# 20200614.net
KiCad netlist of a schematic drawn in Altium Designer
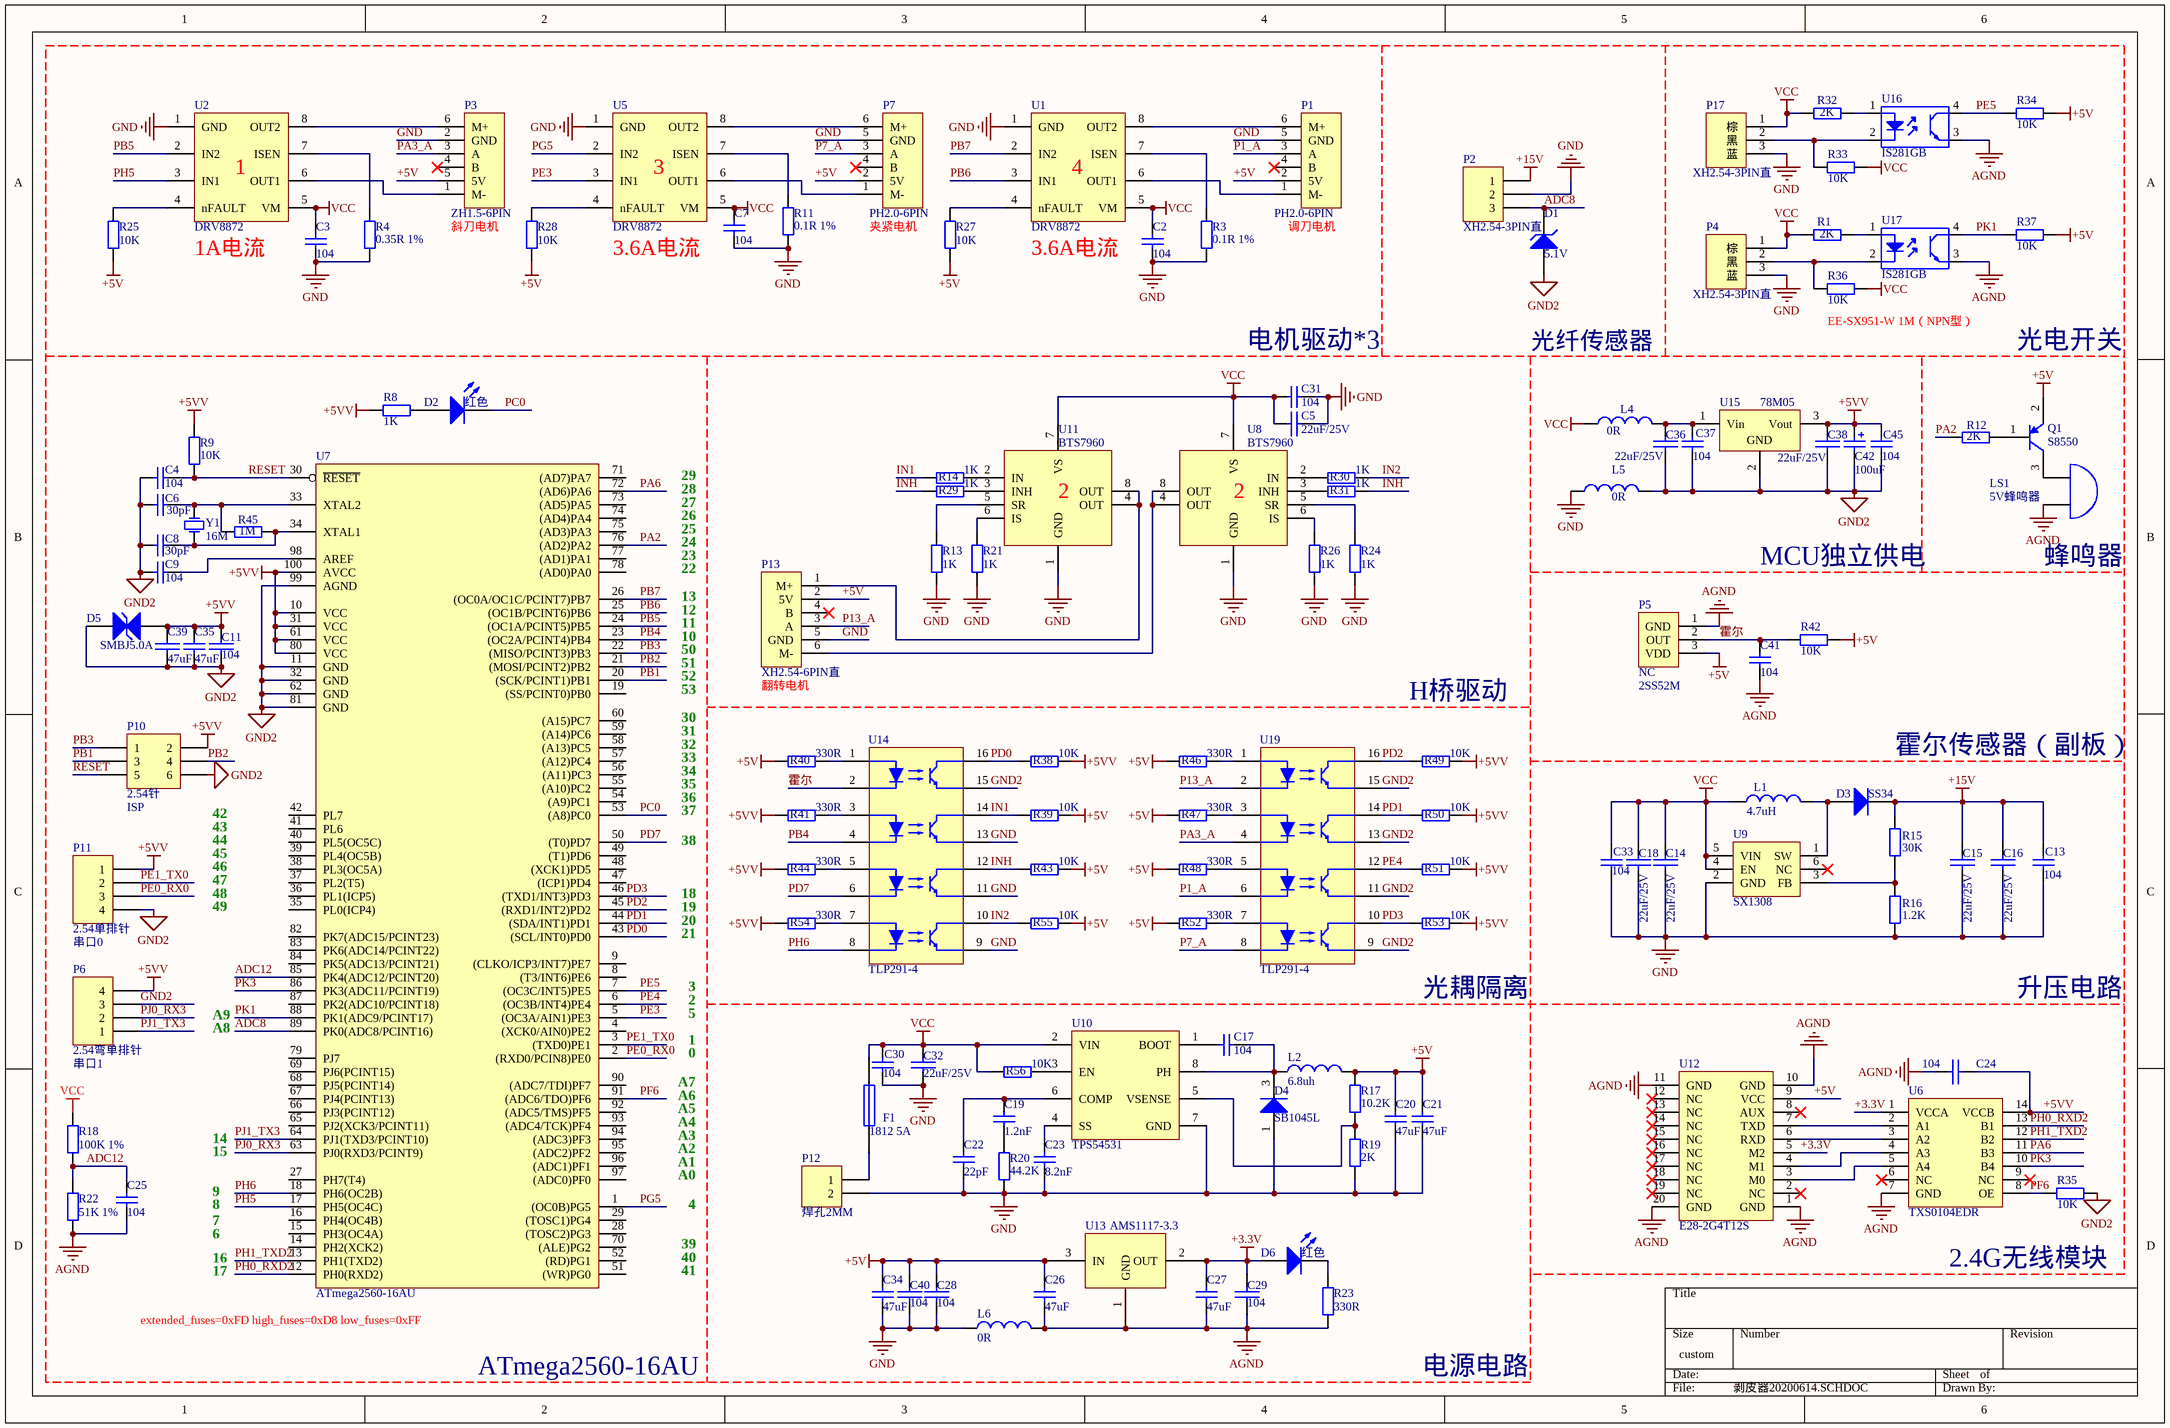
[diagram p0: 剥皮器20200614.SCHDOC]

(export (version "E")
  (design (tool "Eeschema 10.0.6"))
  (components
    (comp (ref "C2")
      (value "104")
      (footprint "0805-C")
      (description "Capacitor")
      (fields (field (name "PUBLISHER") "Altium Limited"))
      (libsource (lib "Miscellaneous Devices") (part "Cap"))
    )
    (comp (ref "C3")
      (value "104")
      (footprint "0805-C")
      (description "Capacitor")
      (fields (field (name "PUBLISHER") "Altium Limited"))
      (libsource (lib "Miscellaneous Devices") (part "Cap"))
    )
    (comp (ref "C4")
      (value "104")
      (footprint "0805-C")
      (description "Capacitor")
      (fields (field (name "PUBLISHER") "Altium Limited"))
      (libsource (lib "Miscellaneous Devices") (part "Cap"))
    )
    (comp (ref "C5")
      (value "22uF/25V")
      (footprint "1206-C")
      (description "Capacitor")
      (libsource (lib "*") (part "CAP"))
    )
    (comp (ref "C6")
      (value "30pF")
      (footprint "0805-C")
      (description "Capacitor")
      (fields (field (name "PUBLISHER") "Altium Limited"))
      (libsource (lib "Miscellaneous Devices") (part "Cap"))
    )
    (comp (ref "C7")
      (value "104")
      (footprint "0805-C")
      (description "Capacitor")
      (fields (field (name "PUBLISHER") "Altium Limited"))
      (libsource (lib "Miscellaneous Devices") (part "Cap"))
    )
    (comp (ref "C8")
      (value "30pF")
      (footprint "0805-C")
      (description "Capacitor")
      (fields (field (name "PUBLISHER") "Altium Limited"))
      (libsource (lib "Miscellaneous Devices") (part "Cap"))
    )
    (comp (ref "C9")
      (value "104")
      (footprint "0805-C")
      (description "Capacitor")
      (fields (field (name "PUBLISHER") "Altium Limited"))
      (libsource (lib "Miscellaneous Devices") (part "Cap"))
    )
    (comp (ref "C11")
      (value "104")
      (footprint "0805-C")
      (description "Capacitor")
      (libsource (lib "*") (part "CAP"))
    )
    (comp (ref "C13")
      (value "104")
      (footprint "0805-C")
      (description "Capacitor")
      (fields (field (name "PUBLISHER") "Altium Limited"))
      (libsource (lib "Miscellaneous Devices") (part "Cap"))
    )
    (comp (ref "C14")
      (value "22uF/25V")
      (footprint "1206-C")
      (description "Capacitor")
      (libsource (lib "*") (part "CAP"))
    )
    (comp (ref "C15")
      (value "22uF/25V")
      (footprint "1206-C")
      (description "Capacitor")
      (libsource (lib "*") (part "CAP"))
    )
    (comp (ref "C16")
      (value "22uF/25V")
      (footprint "1206-C")
      (description "Capacitor")
      (libsource (lib "*") (part "CAP"))
    )
    (comp (ref "C17")
      (value "104")
      (footprint "0805-C")
      (description "Capacitor")
      (fields (field (name "PUBLISHER") "Altium Limited"))
      (libsource (lib "Miscellaneous Devices") (part "Cap"))
    )
    (comp (ref "C18")
      (value "22uF/25V")
      (footprint "1206-C")
      (description "Capacitor")
      (libsource (lib "*") (part "CAP"))
    )
    (comp (ref "C19")
      (value "1.2nF")
      (footprint "0805-C")
      (description "Capacitor")
      (fields (field (name "PUBLISHER") "Altium Limited"))
      (libsource (lib "Miscellaneous Devices") (part "Cap"))
    )
    (comp (ref "C20")
      (value "47uF")
      (footprint "0805-C")
      (description "Capacitor")
      (fields (field (name "PUBLISHER") "Altium Limited"))
      (libsource (lib "Miscellaneous Devices") (part "Cap"))
    )
    (comp (ref "C21")
      (value "47uF")
      (footprint "0805-C")
      (description "Capacitor")
      (fields (field (name "PUBLISHER") "Altium Limited"))
      (libsource (lib "Miscellaneous Devices") (part "Cap"))
    )
    (comp (ref "C22")
      (value "22pF")
      (footprint "0805-C")
      (description "Capacitor")
      (fields (field (name "PUBLISHER") "Altium Limited"))
      (libsource (lib "Miscellaneous Devices") (part "Cap"))
    )
    (comp (ref "C23")
      (value "8.2nF")
      (footprint "0805-C")
      (description "Capacitor")
      (fields (field (name "PUBLISHER") "Altium Limited"))
      (libsource (lib "Miscellaneous Devices") (part "Cap"))
    )
    (comp (ref "C24")
      (value "104")
      (footprint "0805-C")
      (description "Capacitor")
      (libsource (lib "*") (part "CAP"))
    )
    (comp (ref "C25")
      (value "104")
      (footprint "0805-C")
      (description "Capacitor")
      (fields (field (name "PUBLISHER") "Altium Limited"))
      (libsource (lib "Miscellaneous Devices") (part "Cap"))
    )
    (comp (ref "C26")
      (value "47uF")
      (footprint "0805-C")
      (description "Capacitor")
      (fields (field (name "PUBLISHER") "Altium Limited"))
      (libsource (lib "Miscellaneous Devices") (part "Cap"))
    )
    (comp (ref "C27")
      (value "47uF")
      (footprint "0805-C")
      (description "Capacitor")
      (fields (field (name "PUBLISHER") "Altium Limited"))
      (libsource (lib "Miscellaneous Devices") (part "Cap"))
    )
    (comp (ref "C28")
      (value "104")
      (footprint "0805-C")
      (description "Capacitor")
      (libsource (lib "*") (part "CAP"))
    )
    (comp (ref "C29")
      (value "104")
      (footprint "0805-C")
      (description "Capacitor")
      (libsource (lib "*") (part "CAP"))
    )
    (comp (ref "C30")
      (value "104")
      (footprint "0805-C")
      (description "Capacitor")
      (fields (field (name "PUBLISHER") "Altium Limited"))
      (libsource (lib "Miscellaneous Devices") (part "Cap"))
    )
    (comp (ref "C31")
      (value "104")
      (footprint "0805-C")
      (description "Capacitor")
      (fields (field (name "PUBLISHER") "Altium Limited"))
      (libsource (lib "Miscellaneous Devices") (part "Cap"))
    )
    (comp (ref "C32")
      (value "22uF/25V")
      (footprint "1206-C")
      (description "Capacitor")
      (libsource (lib "*") (part "CAP"))
    )
    (comp (ref "C33")
      (value "104")
      (footprint "0805-C")
      (description "Capacitor")
      (fields (field (name "PUBLISHER") "Altium Limited"))
      (libsource (lib "Miscellaneous Devices") (part "Cap"))
    )
    (comp (ref "C34")
      (value "47uF")
      (footprint "0805-C")
      (description "Capacitor")
      (fields (field (name "PUBLISHER") "Altium Limited"))
      (libsource (lib "Miscellaneous Devices") (part "Cap"))
    )
    (comp (ref "C35")
      (value "47uF")
      (footprint "0805-C")
      (description "Capacitor")
      (fields (field (name "PUBLISHER") "Altium Limited"))
      (libsource (lib "Miscellaneous Devices") (part "Cap"))
    )
    (comp (ref "C36")
      (value "22uF/25V")
      (footprint "1206-C")
      (description "Capacitor")
      (libsource (lib "*") (part "CAP"))
    )
    (comp (ref "C37")
      (value "104")
      (footprint "0805-C")
      (description "Capacitor")
      (fields (field (name "PUBLISHER") "Altium Limited"))
      (libsource (lib "Miscellaneous Devices") (part "Cap"))
    )
    (comp (ref "C38")
      (value "22uF/25V")
      (footprint "1206-C")
      (description "Capacitor")
      (libsource (lib "*") (part "CAP"))
    )
    (comp (ref "C39")
      (value "47uF")
      (footprint "0805-C")
      (description "Capacitor")
      (libsource (lib "*") (part "CAP"))
    )
    (comp (ref "C40")
      (value "104")
      (footprint "0805-C")
      (description "Capacitor")
      (libsource (lib "*") (part "CAP"))
    )
    (comp (ref "C41")
      (value "104")
      (footprint "0805-C")
      (description "Capacitor")
      (fields (field (name "PUBLISHER") "Altium Limited"))
      (libsource (lib "Miscellaneous Devices") (part "Cap"))
    )
    (comp (ref "C42")
      (value "100uF")
      (footprint "LC-CASE-C_6032")
      (description "Polarized Capacitor (Axial)")
      (fields (field (name "PUBLISHER") "Altium Limited"))
      (libsource (lib "Miscellaneous Devices") (part "Cap Pol2"))
    )
    (comp (ref "C45")
      (value "104")
      (footprint "0805-C")
      (description "Capacitor")
      (fields (field (name "PUBLISHER") "Altium Limited"))
      (libsource (lib "Miscellaneous Devices") (part "Cap"))
    )
    (comp (ref "D1")
      (value "5.1V")
      (footprint "LC-LL-34")
      (description "Zener Diode")
      (fields (field (name "PUBLISHER") "Altium Limited"))
      (libsource (lib "Miscellaneous Devices") (part "D Zener"))
    )
    (comp (ref "D2")
      (value "红色")
      (footprint "0805-LED")
      (description "Typical INFRARED GaAs LED")
      (fields (field (name "PUBLISHER") "Altium Limited"))
      (libsource (lib "Miscellaneous Devices") (part "LED0"))
    )
    (comp (ref "D3")
      (value "SS34")
      (footprint "SMA - JW")
      (description "1 Amp General Purpose Rectifier")
      (fields (field (name "PUBLISHER") "Altium Limited"))
      (libsource (lib "Miscellaneous Devices") (part "Diode 1N4007"))
    )
    (comp (ref "D4")
      (value "SB1045L")
      (footprint "TO-277")
      (description "1 Amp General Purpose Rectifier")
      (fields (field (name "PUBLISHER") "Altium Limited"))
      (libsource (lib "Miscellaneous Devices") (part "Diode 1N4001"))
    )
    (comp (ref "D5")
      (value "SMBJ5.0A")
      (footprint "LC-SMB(DO-214AA)_S2")
      (description "TVS")
      (libsource (lib "JW专用元件库") (part "TVS"))
    )
    (comp (ref "D6")
      (value "红色")
      (footprint "0805-LED")
      (description "Typical INFRARED GaAs LED")
      (fields (field (name "PUBLISHER") "Altium Limited"))
      (libsource (lib "Miscellaneous Devices") (part "LED0"))
    )
    (comp (ref "F1")
      (value "1812 5A")
      (footprint "LC-1812_R")
      (description "Fuse")
      (fields (field (name "PUBLISHER") "Altium Limited"))
      (libsource (lib "Miscellaneous Devices") (part "Fuse 1"))
    )
    (comp (ref "L1")
      (value "4.7uH")
      (footprint "7*7*4电感")
      (description "Inductor")
      (fields (field (name "PUBLISHER") "Altium Limited"))
      (libsource (lib "Miscellaneous Devices") (part "Inductor"))
    )
    (comp (ref "L2")
      (value "6.8uh")
      (footprint "7*7*4电感")
      (description "Inductor")
      (fields (field (name "PUBLISHER") "Altium Limited"))
      (libsource (lib "Miscellaneous Devices") (part "Inductor"))
    )
    (comp (ref "L4")
      (value "0R")
      (footprint "0805-R")
      (description "Inductor")
      (fields (field (name "PUBLISHER") "Altium Limited"))
      (libsource (lib "Miscellaneous Devices") (part "Inductor"))
    )
    (comp (ref "L5")
      (value "0R")
      (footprint "0805-R")
      (description "Inductor")
      (fields (field (name "PUBLISHER") "Altium Limited"))
      (libsource (lib "Miscellaneous Devices") (part "Inductor"))
    )
    (comp (ref "L6")
      (value "0R")
      (footprint "0805-R")
      (description "Inductor")
      (fields (field (name "PUBLISHER") "Altium Limited"))
      (libsource (lib "Miscellaneous Devices") (part "Inductor"))
    )
    (comp (ref "LS1")
      (value "5V蜂鸣器")
      (footprint "蜂鸣器0905")
      (description "Electrical Bell")
      (fields (field (name "PUBLISHER") "Altium Limited"))
      (libsource (lib "Miscellaneous Devices") (part "Bell"))
    )
    (comp (ref "P1")
      (value "PH2.0-6PIN")
      (footprint "PH2.0-6PIN")
      (description "Header, 6-Pin")
      (fields (field (name "PUBLISHER") "Altium Limited"))
      (libsource (lib "Miscellaneous Connectors") (part "Header 6"))
    )
    (comp (ref "P2")
      (value "XH2.54-3PIN直")
      (footprint "XH2.54-3PIN直")
      (description "Header, 3-Pin")
      (fields (field (name "PUBLISHER") "Altium Limited"))
      (libsource (lib "") (part "Header 3_2"))
    )
    (comp (ref "P3")
      (value "ZH1.5-6PIN")
      (footprint "ZH1.5-6PIN")
      (description "Header, 6-Pin")
      (fields (field (name "PUBLISHER") "Altium Limited"))
      (libsource (lib "") (part "Header 6_2"))
    )
    (comp (ref "P4")
      (value "XH2.54-3PIN直")
      (footprint "XH2.54-3PIN直")
      (description "Header, 3-Pin")
      (fields (field (name "PUBLISHER") "Altium Limited"))
      (libsource (lib "") (part "Header 3_1"))
    )
    (comp (ref "P5")
      (value "NC")
      (footprint "TO-92—_三极管")
      (description "Header, 3-Pin")
      (fields (field (name "PUBLISHER") "2SS52M"))
      (libsource (lib "Miscellaneous Connectors") (part "Header 3"))
    )
    (comp (ref "P6")
      (value "2.54弯单排针")
      (footprint "HDR1X4H")
      (description "Header, 4-Pin")
      (fields (field (name "ALTIUM_UNNAMED_1") "串口1") (field (name "PUBLISHER") "Altium Limited"))
      (libsource (lib "Miscellaneous Connectors") (part "Header 4"))
    )
    (comp (ref "P7")
      (value "PH2.0-6PIN")
      (footprint "PH2.0-6PIN")
      (description "Header, 6-Pin")
      (fields (field (name "PUBLISHER") "Altium Limited"))
      (libsource (lib "Miscellaneous Connectors") (part "Header 6"))
    )
    (comp (ref "P10")
      (value "2.54针")
      (footprint "HDR2X3")
      (description "Header, 3-Pin, Dual row")
      (fields (field (name "ALTIUM_UNNAMED_1") "ISP") (field (name "PUBLISHER") "Altium Limited"))
      (libsource (lib "Miscellaneous Connectors") (part "Header 3X2"))
    )
    (comp (ref "P11")
      (value "2.54单排针")
      (footprint "HDR1X4")
      (description "Header, 4-Pin")
      (fields (field (name "ALTIUM_UNNAMED_1") "串口0") (field (name "PUBLISHER") "Altium Limited"))
      (libsource (lib "") (part "Header 4_1"))
    )
    (comp (ref "P12")
      (value "焊孔2MM")
      (footprint "HDR1X2")
      (description "Header, 2-Pin")
      (fields (field (name "PUBLISHER") "Altium Limited"))
      (libsource (lib "Miscellaneous Connectors") (part "Header 2"))
    )
    (comp (ref "P13")
      (value "XH2.54-6PIN直")
      (footprint "XH2.54-6PIN直")
      (description "Header, 6-Pin")
      (fields (field (name "PUBLISHER") "Altium Limited"))
      (libsource (lib "") (part "Header 6_1"))
    )
    (comp (ref "P17")
      (value "XH2.54-3PIN直")
      (footprint "XH2.54-3PIN直")
      (description "Header, 3-Pin")
      (fields (field (name "PUBLISHER") "Altium Limited"))
      (libsource (lib "") (part "Header 3_1"))
    )
    (comp (ref "Q1")
      (value "S8550")
      (footprint "SOT--23")
      (description "PNP General Purpose Amplifier")
      (fields (field (name "PUBLISHER") "Altium Limited"))
      (libsource (lib "Miscellaneous Devices") (part "2N3906"))
    )
    (comp (ref "R1")
      (value "2K")
      (footprint "0805-R")
      (description "Resistor")
      (fields (field (name "PUBLISHER") "Altium Limited"))
      (libsource (lib "") (part "Res2_2"))
    )
    (comp (ref "R3")
      (value "0.1R 1%")
      (footprint "2512-R")
      (description "Resistor")
      (fields (field (name "PUBLISHER") "Altium Limited"))
      (libsource (lib "Miscellaneous Devices") (part "Res2"))
    )
    (comp (ref "R4")
      (value "0.35R 1%")
      (footprint "2512-R")
      (description "Resistor")
      (fields (field (name "PUBLISHER") "Altium Limited"))
      (libsource (lib "Miscellaneous Devices") (part "Res2"))
    )
    (comp (ref "R8")
      (value "1K")
      (footprint "0805-R")
      (description "Resistor")
      (fields (field (name "PUBLISHER") "Altium Limited"))
      (libsource (lib "") (part "Res2_1"))
    )
    (comp (ref "R9")
      (value "10K")
      (footprint "0805-R")
      (description "Resistor")
      (fields (field (name "PUBLISHER") "Altium Limited"))
      (libsource (lib "Miscellaneous Devices") (part "Res2"))
    )
    (comp (ref "R11")
      (value "0.1R 1%")
      (footprint "2512-R")
      (description "Resistor")
      (fields (field (name "PUBLISHER") "Altium Limited"))
      (libsource (lib "Miscellaneous Devices") (part "Res2"))
    )
    (comp (ref "R12")
      (value "2K")
      (footprint "0805-R")
      (description "Resistor")
      (fields (field (name "PUBLISHER") "Altium Limited"))
      (libsource (lib "") (part "Res2_1"))
    )
    (comp (ref "R13")
      (value "1K")
      (footprint "0805-R")
      (description "Resistor")
      (fields (field (name "PUBLISHER") "Altium Limited"))
      (libsource (lib "Miscellaneous Devices") (part "Res2"))
    )
    (comp (ref "R14")
      (value "1K")
      (footprint "0805-R")
      (description "Resistor")
      (fields (field (name "PUBLISHER") "Altium Limited"))
      (libsource (lib "") (part "Res2_1"))
    )
    (comp (ref "R15")
      (value "30K")
      (footprint "0805-R")
      (description "Resistor")
      (fields (field (name "PUBLISHER") "Altium Limited"))
      (libsource (lib "") (part "Res2_3"))
    )
    (comp (ref "R16")
      (value "1.2K")
      (footprint "0805-R")
      (description "Resistor")
      (fields (field (name "PUBLISHER") "Altium Limited"))
      (libsource (lib "") (part "Res2_3"))
    )
    (comp (ref "R17")
      (value "10.2K")
      (footprint "0805-R")
      (description "Resistor")
      (fields (field (name "PUBLISHER") "Altium Limited"))
      (libsource (lib "Miscellaneous Devices") (part "Res2"))
    )
    (comp (ref "R18")
      (value "100K 1%")
      (footprint "0805-R")
      (description "Resistor")
      (fields (field (name "PUBLISHER") "Altium Limited"))
      (libsource (lib "Miscellaneous Devices") (part "Res2"))
    )
    (comp (ref "R19")
      (value "2K")
      (footprint "0805-R")
      (description "Resistor")
      (fields (field (name "PUBLISHER") "Altium Limited"))
      (libsource (lib "Miscellaneous Devices") (part "Res2"))
    )
    (comp (ref "R20")
      (value "44.2K")
      (footprint "0805-R")
      (description "Resistor")
      (fields (field (name "PUBLISHER") "Altium Limited"))
      (libsource (lib "Miscellaneous Devices") (part "Res2"))
    )
    (comp (ref "R21")
      (value "1K")
      (footprint "0805-R")
      (description "Resistor")
      (fields (field (name "PUBLISHER") "Altium Limited"))
      (libsource (lib "Miscellaneous Devices") (part "Res2"))
    )
    (comp (ref "R22")
      (value "51K 1%")
      (footprint "0805-R")
      (description "Resistor")
      (fields (field (name "PUBLISHER") "Altium Limited"))
      (libsource (lib "Miscellaneous Devices") (part "Res2"))
    )
    (comp (ref "R23")
      (value "330R")
      (footprint "0805-R")
      (description "Resistor")
      (fields (field (name "PUBLISHER") "Altium Limited"))
      (libsource (lib "") (part "Res2_3"))
    )
    (comp (ref "R24")
      (value "1K")
      (footprint "0805-R")
      (description "Resistor")
      (fields (field (name "PUBLISHER") "Altium Limited"))
      (libsource (lib "") (part "Res2_2"))
    )
    (comp (ref "R25")
      (value "10K")
      (footprint "0805-R")
      (description "Resistor")
      (fields (field (name "PUBLISHER") "Altium Limited"))
      (libsource (lib "Miscellaneous Devices") (part "Res2"))
    )
    (comp (ref "R26")
      (value "1K")
      (footprint "0805-R")
      (description "Resistor")
      (fields (field (name "PUBLISHER") "Altium Limited"))
      (libsource (lib "") (part "Res2_2"))
    )
    (comp (ref "R27")
      (value "10K")
      (footprint "0805-R")
      (description "Resistor")
      (fields (field (name "PUBLISHER") "Altium Limited"))
      (libsource (lib "Miscellaneous Devices") (part "Res2"))
    )
    (comp (ref "R28")
      (value "10K")
      (footprint "0805-R")
      (description "Resistor")
      (fields (field (name "PUBLISHER") "Altium Limited"))
      (libsource (lib "Miscellaneous Devices") (part "Res2"))
    )
    (comp (ref "R29")
      (value "1K")
      (footprint "0805-R")
      (description "Resistor")
      (fields (field (name "PUBLISHER") "Altium Limited"))
      (libsource (lib "") (part "Res2_1"))
    )
    (comp (ref "R30")
      (value "1K")
      (footprint "0805-R")
      (description "Resistor")
      (fields (field (name "PUBLISHER") "Altium Limited"))
      (libsource (lib "") (part "Res2_1"))
    )
    (comp (ref "R31")
      (value "1K")
      (footprint "0805-R")
      (description "Resistor")
      (fields (field (name "PUBLISHER") "Altium Limited"))
      (libsource (lib "") (part "Res2_1"))
    )
    (comp (ref "R32")
      (value "2K")
      (footprint "0805-R")
      (description "Resistor")
      (fields (field (name "PUBLISHER") "Altium Limited"))
      (libsource (lib "") (part "Res2_2"))
    )
    (comp (ref "R33")
      (value "10K")
      (footprint "0805-R")
      (description "Resistor")
      (fields (field (name "PUBLISHER") "Altium Limited"))
      (libsource (lib "") (part "Res2_1"))
    )
    (comp (ref "R34")
      (value "10K")
      (footprint "0805-R")
      (description "Resistor")
      (fields (field (name "PUBLISHER") "Altium Limited"))
      (libsource (lib "") (part "Res2_2"))
    )
    (comp (ref "R35")
      (value "10K")
      (footprint "0805-R")
      (description "Resistor")
      (fields (field (name "PUBLISHER") "Altium Limited"))
      (libsource (lib "") (part "Res2_1"))
    )
    (comp (ref "R36")
      (value "10K")
      (footprint "0805-R")
      (description "Resistor")
      (fields (field (name "PUBLISHER") "Altium Limited"))
      (libsource (lib "") (part "Res2_1"))
    )
    (comp (ref "R37")
      (value "10K")
      (footprint "0805-R")
      (description "Resistor")
      (fields (field (name "PUBLISHER") "Altium Limited"))
      (libsource (lib "") (part "Res2_2"))
    )
    (comp (ref "R38")
      (value "10K")
      (footprint "0805-R")
      (description "Resistor")
      (fields (field (name "PUBLISHER") "Altium Limited"))
      (libsource (lib "") (part "Res2_1"))
    )
    (comp (ref "R39")
      (value "10K")
      (footprint "0805-R")
      (description "Resistor")
      (fields (field (name "PUBLISHER") "Altium Limited"))
      (libsource (lib "") (part "Res2_1"))
    )
    (comp (ref "R40")
      (value "330R")
      (footprint "0805-R")
      (description "Resistor")
      (fields (field (name "PUBLISHER") "Altium Limited"))
      (libsource (lib "") (part "Res2_1"))
    )
    (comp (ref "R41")
      (value "330R")
      (footprint "0805-R")
      (description "Resistor")
      (fields (field (name "PUBLISHER") "Altium Limited"))
      (libsource (lib "") (part "Res2_1"))
    )
    (comp (ref "R42")
      (value "10K")
      (footprint "0805-R")
      (description "Resistor")
      (fields (field (name "PUBLISHER") "Altium Limited"))
      (libsource (lib "") (part "Res2_1"))
    )
    (comp (ref "R43")
      (value "10K")
      (footprint "0805-R")
      (description "Resistor")
      (fields (field (name "PUBLISHER") "Altium Limited"))
      (libsource (lib "") (part "Res2_1"))
    )
    (comp (ref "R44")
      (value "330R")
      (footprint "0805-R")
      (description "Resistor")
      (fields (field (name "PUBLISHER") "Altium Limited"))
      (libsource (lib "") (part "Res2_1"))
    )
    (comp (ref "R45")
      (value "1M")
      (footprint "0805-R")
      (description "Resistor")
      (fields (field (name "PUBLISHER") "Altium Limited"))
      (libsource (lib "") (part "Res2_2"))
    )
    (comp (ref "R46")
      (value "330R")
      (footprint "0805-R")
      (description "Resistor")
      (fields (field (name "PUBLISHER") "Altium Limited"))
      (libsource (lib "") (part "Res2_1"))
    )
    (comp (ref "R47")
      (value "330R")
      (footprint "0805-R")
      (description "Resistor")
      (fields (field (name "PUBLISHER") "Altium Limited"))
      (libsource (lib "") (part "Res2_1"))
    )
    (comp (ref "R48")
      (value "330R")
      (footprint "0805-R")
      (description "Resistor")
      (fields (field (name "PUBLISHER") "Altium Limited"))
      (libsource (lib "") (part "Res2_1"))
    )
    (comp (ref "R49")
      (value "10K")
      (footprint "0805-R")
      (description "Resistor")
      (fields (field (name "PUBLISHER") "Altium Limited"))
      (libsource (lib "") (part "Res2_1"))
    )
    (comp (ref "R50")
      (value "10K")
      (footprint "0805-R")
      (description "Resistor")
      (fields (field (name "PUBLISHER") "Altium Limited"))
      (libsource (lib "") (part "Res2_1"))
    )
    (comp (ref "R51")
      (value "10K")
      (footprint "0805-R")
      (description "Resistor")
      (fields (field (name "PUBLISHER") "Altium Limited"))
      (libsource (lib "") (part "Res2_1"))
    )
    (comp (ref "R52")
      (value "330R")
      (footprint "0805-R")
      (description "Resistor")
      (fields (field (name "PUBLISHER") "Altium Limited"))
      (libsource (lib "") (part "Res2_1"))
    )
    (comp (ref "R53")
      (value "10K")
      (footprint "0805-R")
      (description "Resistor")
      (fields (field (name "PUBLISHER") "Altium Limited"))
      (libsource (lib "") (part "Res2_1"))
    )
    (comp (ref "R54")
      (value "330R")
      (footprint "0805-R")
      (description "Resistor")
      (fields (field (name "PUBLISHER") "Altium Limited"))
      (libsource (lib "") (part "Res2_1"))
    )
    (comp (ref "R55")
      (value "10K")
      (footprint "0805-R")
      (description "Resistor")
      (fields (field (name "PUBLISHER") "Altium Limited"))
      (libsource (lib "") (part "Res2_1"))
    )
    (comp (ref "R56")
      (value "10K")
      (footprint "0805-R")
      (description "Resistor")
      (fields (field (name "PUBLISHER") "Altium Limited"))
      (libsource (lib "") (part "Res2_1"))
    )
    (comp (ref "U1")
      (value "DRV8872")
      (footprint "SOP-8带散热")
      (description "6N137")
      (libsource (lib "JW专用库") (part "6N137"))
    )
    (comp (ref "U2")
      (value "DRV8872")
      (footprint "SOP-8带散热")
      (description "6N137")
      (libsource (lib "JW专用库") (part "6N137"))
    )
    (comp (ref "U5")
      (value "DRV8872")
      (footprint "SOP-8带散热")
      (description "6N137")
      (libsource (lib "JW专用库") (part "6N137"))
    )
    (comp (ref "U6")
      (value "TXS0104EDR")
      (footprint "LC-SOIC-14_150mil")
      (libsource (lib "*") (part "TXS0104EDR"))
    )
    (comp (ref "U7")
      (value "ATmega2560-16AU")
      (footprint "LC-LQFP-100_14x14x05P")
      (libsource (lib "*") (part "Arduino MEGA 2560"))
    )
    (comp (ref "U8") (value "BTS7960") (footprint "LC-TO-263-7") (libsource (lib "") (part "BTS7960_1")))
    (comp (ref "U9") (value "SX1308") (footprint "SOT-23-6") (libsource (lib "JW专用库") (part "SX1308")))
    (comp (ref "U10") (value "TPS54531") (footprint "SOP-8带散热") (libsource (lib "*") (part "TPS54531")))
    (comp (ref "U11") (value "BTS7960") (footprint "LC-TO-263-7") (libsource (lib "*") (part "BTS7960")))
    (comp (ref "U12")
      (value "E28-2G4T12S")
      (footprint "E28-2G4T12S")
      (libsource (lib "JW专用元件库") (part "E43-433T13S"))
    )
    (comp (ref "U13") (value "AMS1117-3.3") (footprint "SOT--223") (libsource (lib "*") (part "AS1117")))
    (comp (ref "U14")
      (value "TLP291-4")
      (footprint "TLP291-4")
      (description "Photocouplers GaAs Infrared LED & Photo Transistor")
      (libsource (lib "YS_STM32F407_MC") (part "TLP291-4"))
    )
    (comp (ref "U15")
      (value "78M05")
      (footprint "TO-252")
      (description "Voltage Regulator")
      (fields (field (name "PUBLISHER") "Altium Limited"))
      (libsource (lib "Miscellaneous Devices") (part "Volt Reg"))
    )
    (comp (ref "U16") (value "IS281GB") (footprint "LC-SOP-4_P1.27") (libsource (lib "*") (part "TLP521-1")))
    (comp (ref "U17") (value "IS281GB") (footprint "LC-SOP-4_P1.27") (libsource (lib "*") (part "TLP521-1")))
    (comp (ref "U19")
      (value "TLP291-4")
      (footprint "TLP291-4")
      (description "Photocouplers GaAs Infrared LED & Photo Transistor")
      (libsource (lib "YS_STM32F407_MC") (part "TLP291-4"))
    )
    (comp (ref "Y1")
      (value "16M")
      (footprint "LC-SMD-5032_2P")
      (description "Crystal Oscillator")
      (fields (field (name "PUBLISHER") "Altium Limited"))
      (libsource (lib "Miscellaneous Devices") (part "XTAL"))
    )
  )
  (nets
    (net (code "1") (name "+3.3V") (class "Default")
      (node (ref "C27") (pin "2") (pinfunction "2_2") (pintype "passive"))
      (node (ref "C29") (pin "1") (pinfunction "1_1") (pintype "passive"))
      (node (ref "D6") (pin "1") (pinfunction "A_1") (pintype "passive"))
      (node (ref "U12") (pin "5") (pinfunction "M2_5") (pintype "passive"))
      (node (ref "U13") (pin "2") (pinfunction "OUT_2") (pintype "passive"))
      (node (ref "U6") (pin "1") (pinfunction "VCCA_1") (pintype "passive"))
    )
    (net (code "2") (name "+5V") (class "Default")
      (node (ref "C20") (pin "2") (pinfunction "2_2") (pintype "passive"))
      (node (ref "C21") (pin "2") (pinfunction "2_2") (pintype "passive"))
      (node (ref "C26") (pin "2") (pinfunction "2_2") (pintype "passive"))
      (node (ref "C28") (pin "1") (pinfunction "1_1") (pintype "passive"))
      (node (ref "C34") (pin "2") (pinfunction "2_2") (pintype "passive"))
      (node (ref "C40") (pin "1") (pinfunction "1_1") (pintype "passive"))
      (node (ref "L2") (pin "2") (pinfunction "2_2") (pintype "passive"))
      (node (ref "P1") (pin "2") (pinfunction "5V_2") (pintype "passive"))
      (node (ref "P13") (pin "2") (pinfunction "5V_2") (pintype "passive"))
      (node (ref "P3") (pin "5") (pinfunction "5V_5") (pintype "passive"))
      (node (ref "P5") (pin "3") (pinfunction "VDD_3") (pintype "passive"))
      (node (ref "P7") (pin "2") (pinfunction "5V_2") (pintype "passive"))
      (node (ref "Q1") (pin "2") (pinfunction "E_2") (pintype "passive"))
      (node (ref "R17") (pin "2") (pinfunction "2_2") (pintype "passive"))
      (node (ref "R25") (pin "1") (pinfunction "1_1") (pintype "passive"))
      (node (ref "R27") (pin "1") (pinfunction "1_1") (pintype "passive"))
      (node (ref "R28") (pin "1") (pinfunction "1_1") (pintype "passive"))
      (node (ref "R34") (pin "2") (pinfunction "2_2") (pintype "passive"))
      (node (ref "R37") (pin "2") (pinfunction "2_2") (pintype "passive"))
      (node (ref "R39") (pin "1") (pinfunction "1_1") (pintype "passive"))
      (node (ref "R40") (pin "2") (pinfunction "2_2") (pintype "passive"))
      (node (ref "R42") (pin "1") (pinfunction "1_1") (pintype "passive"))
      (node (ref "R43") (pin "1") (pinfunction "1_1") (pintype "passive"))
      (node (ref "R46") (pin "2") (pinfunction "2_2") (pintype "passive"))
      (node (ref "R47") (pin "2") (pinfunction "2_2") (pintype "passive"))
      (node (ref "R48") (pin "2") (pinfunction "2_2") (pintype "passive"))
      (node (ref "R52") (pin "2") (pinfunction "2_2") (pintype "passive"))
      (node (ref "R55") (pin "1") (pinfunction "1_1") (pintype "passive"))
      (node (ref "U12") (pin "9") (pinfunction "VCC_9") (pintype "passive"))
      (node (ref "U13") (pin "3") (pinfunction "IN_3") (pintype "passive"))
    )
    (net (code "3") (name "+5VV") (class "Default")
      (node (ref "C11") (pin "1") (pinfunction "1_1") (pintype "passive"))
      (node (ref "C24") (pin "2") (pinfunction "2_2") (pintype "passive"))
      (node (ref "C35") (pin "2") (pinfunction "2_2") (pintype "passive"))
      (node (ref "C38") (pin "1") (pinfunction "1_1") (pintype "passive"))
      (node (ref "C39") (pin "2") (pinfunction "2_2") (pintype "passive"))
      (node (ref "C42") (pin "1") (pinfunction "1_1") (pintype "passive"))
      (node (ref "C45") (pin "2") (pinfunction "2_2") (pintype "passive"))
      (node (ref "D5") (pin "1") (pinfunction "A_1") (pintype "passive"))
      (node (ref "P10") (pin "2") (pinfunction "2_2") (pintype "passive"))
      (node (ref "P11") (pin "1") (pinfunction "1_1") (pintype "passive"))
      (node (ref "P6") (pin "4") (pinfunction "4_4") (pintype "passive"))
      (node (ref "R38") (pin "1") (pinfunction "1_1") (pintype "passive"))
      (node (ref "R41") (pin "2") (pinfunction "2_2") (pintype "passive"))
      (node (ref "R44") (pin "2") (pinfunction "2_2") (pintype "passive"))
      (node (ref "R49") (pin "1") (pinfunction "1_1") (pintype "passive"))
      (node (ref "R50") (pin "1") (pinfunction "1_1") (pintype "passive"))
      (node (ref "R51") (pin "1") (pinfunction "1_1") (pintype "passive"))
      (node (ref "R53") (pin "1") (pinfunction "1_1") (pintype "passive"))
      (node (ref "R54") (pin "2") (pinfunction "2_2") (pintype "passive"))
      (node (ref "R8") (pin "2") (pinfunction "2_2") (pintype "passive"))
      (node (ref "R9") (pin "2") (pinfunction "2_2") (pintype "passive"))
      (node (ref "U15") (pin "3") (pinfunction "Vout_3") (pintype "passive"))
      (node (ref "U6") (pin "14") (pinfunction "VCCB_14") (pintype "passive"))
      (node (ref "U7") (pin "10") (pinfunction "VCC_10") (pintype "passive"))
      (node (ref "U7") (pin "100") (pinfunction "AVCC_100") (pintype "passive"))
      (node (ref "U7") (pin "31") (pinfunction "VCC_31") (pintype "passive"))
      (node (ref "U7") (pin "61") (pinfunction "VCC_61") (pintype "passive"))
      (node (ref "U7") (pin "80") (pinfunction "VCC_80") (pintype "passive"))
    )
    (net (code "4") (name "+15V") (class "Default")
      (node (ref "C13") (pin "1") (pinfunction "1_1") (pintype "passive"))
      (node (ref "C15") (pin "1") (pinfunction "1_1") (pintype "passive"))
      (node (ref "C16") (pin "1") (pinfunction "1_1") (pintype "passive"))
      (node (ref "D3") (pin "2") (pinfunction "K_2") (pintype "passive"))
      (node (ref "P2") (pin "1") (pinfunction "1_1") (pintype "passive"))
      (node (ref "R15") (pin "1") (pinfunction "1_1") (pintype "passive"))
    )
    (net (code "5") (name "/ADC8") (class "Default")
      (node (ref "D1") (pin "2") (pinfunction "K_2") (pintype "passive"))
      (node (ref "P2") (pin "3") (pinfunction "3_3") (pintype "passive"))
      (node (ref "U7") (pin "89") (pinfunction "PK0(ADC8/PCINT16)_89") (pintype "passive"))
    )
    (net (code "6") (name "/ADC12") (class "Default")
      (node (ref "C25") (pin "1") (pinfunction "1_1") (pintype "passive"))
      (node (ref "R18") (pin "1") (pinfunction "1_1") (pintype "passive"))
      (node (ref "R22") (pin "2") (pinfunction "2_2") (pintype "passive"))
      (node (ref "U7") (pin "85") (pinfunction "PK4(ADC12/PCINT20)_85") (pintype "passive"))
    )
    (net (code "7") (name "/IN1") (class "Default")
      (node (ref "R14") (pin "2") (pinfunction "2_2") (pintype "passive"))
      (node (ref "R39") (pin "2") (pinfunction "2_2") (pintype "passive"))
      (node (ref "U14") (pin "14") (pinfunction "Collector2_14") (pintype "passive"))
    )
    (net (code "8") (name "/IN2") (class "Default")
      (node (ref "R30") (pin "1") (pinfunction "1_1") (pintype "passive"))
      (node (ref "R55") (pin "2") (pinfunction "2_2") (pintype "passive"))
      (node (ref "U14") (pin "10") (pinfunction "Collector4_10") (pintype "passive"))
    )
    (net (code "9") (name "/INH") (class "Default")
      (node (ref "R29") (pin "2") (pinfunction "2_2") (pintype "passive"))
      (node (ref "R31") (pin "1") (pinfunction "1_1") (pintype "passive"))
      (node (ref "R43") (pin "2") (pinfunction "2_2") (pintype "passive"))
      (node (ref "U14") (pin "12") (pinfunction "Collector3_12") (pintype "passive"))
    )
    (net (code "10") (name "/P1_A") (class "Default")
      (node (ref "P1") (pin "3") (pinfunction "A_3") (pintype "passive"))
      (node (ref "U19") (pin "6") (pinfunction "Cathode3_6") (pintype "passive"))
    )
    (net (code "11") (name "/P7_A") (class "Default")
      (node (ref "P7") (pin "3") (pinfunction "A_3") (pintype "passive"))
      (node (ref "U19") (pin "8") (pinfunction "Cathode4_8") (pintype "passive"))
    )
    (net (code "12") (name "/P13_A") (class "Default")
      (node (ref "P13") (pin "3") (pinfunction "A_3") (pintype "passive"))
      (node (ref "U19") (pin "2") (pinfunction "Cathode1_2") (pintype "passive"))
    )
    (net (code "13") (name "/PA2") (class "Default")
      (node (ref "R12") (pin "2") (pinfunction "2_2") (pintype "passive"))
      (node (ref "U7") (pin "76") (pinfunction "(AD2)PA2_76") (pintype "passive"))
    )
    (net (code "14") (name "/PA3_A") (class "Default")
      (node (ref "P3") (pin "3") (pinfunction "A_3") (pintype "passive"))
      (node (ref "U19") (pin "4") (pinfunction "Cathode2_4") (pintype "passive"))
    )
    (net (code "15") (name "/PA6") (class "Default")
      (node (ref "U6") (pin "11") (pinfunction "B3_11") (pintype "passive"))
      (node (ref "U7") (pin "72") (pinfunction "(AD6)PA6_72") (pintype "passive"))
    )
    (net (code "16") (name "/PB1") (class "Default")
      (node (ref "P10") (pin "3") (pinfunction "3_3") (pintype "passive"))
      (node (ref "U7") (pin "20") (pinfunction "(SCK/PCINT1)PB1_20") (pintype "passive"))
    )
    (net (code "17") (name "/PB2") (class "Default")
      (node (ref "P10") (pin "4") (pinfunction "4_4") (pintype "passive"))
      (node (ref "U7") (pin "21") (pinfunction "(MOSI/PCINT2)PB2_21") (pintype "passive"))
    )
    (net (code "18") (name "/PB3") (class "Default")
      (node (ref "P10") (pin "1") (pinfunction "1_1") (pintype "passive"))
      (node (ref "U7") (pin "22") (pinfunction "(MISO/PCINT3)PB3_22") (pintype "passive"))
    )
    (net (code "19") (name "/PB4") (class "Default")
      (node (ref "U14") (pin "4") (pinfunction "Cathode2_4") (pintype "passive"))
      (node (ref "U7") (pin "23") (pinfunction "(OC2A/PCINT4)PB4_23") (pintype "passive"))
    )
    (net (code "20") (name "/PB5") (class "Default")
      (node (ref "U2") (pin "2") (pinfunction "IN2_2") (pintype "passive"))
      (node (ref "U7") (pin "24") (pinfunction "(OC1A/PCINT5)PB5_24") (pintype "passive"))
    )
    (net (code "21") (name "/PB6") (class "Default")
      (node (ref "U1") (pin "3") (pinfunction "IN1_3") (pintype "passive"))
      (node (ref "U7") (pin "25") (pinfunction "(OC1B/PCINT6)PB6_25") (pintype "passive"))
    )
    (net (code "22") (name "/PB7") (class "Default")
      (node (ref "U1") (pin "2") (pinfunction "IN2_2") (pintype "passive"))
      (node (ref "U7") (pin "26") (pinfunction "(OC0A/OC1C/PCINT7)PB7_26") (pintype "passive"))
    )
    (net (code "23") (name "/PC0") (class "Default")
      (node (ref "D2") (pin "2") (pinfunction "K_2") (pintype "passive"))
      (node (ref "U7") (pin "53") (pinfunction "(A8)PC0_53") (pintype "passive"))
    )
    (net (code "24") (name "/PD0") (class "Default")
      (node (ref "R38") (pin "2") (pinfunction "2_2") (pintype "passive"))
      (node (ref "U14") (pin "16") (pinfunction "Collector1_16") (pintype "passive"))
      (node (ref "U7") (pin "43") (pinfunction "(SCL/INT0)PD0_43") (pintype "passive"))
    )
    (net (code "25") (name "/PD1") (class "Default")
      (node (ref "R50") (pin "2") (pinfunction "2_2") (pintype "passive"))
      (node (ref "U19") (pin "14") (pinfunction "Collector2_14") (pintype "passive"))
      (node (ref "U7") (pin "44") (pinfunction "(SDA/INT1)PD1_44") (pintype "passive"))
    )
    (net (code "26") (name "/PD2") (class "Default")
      (node (ref "R49") (pin "2") (pinfunction "2_2") (pintype "passive"))
      (node (ref "U19") (pin "16") (pinfunction "Collector1_16") (pintype "passive"))
      (node (ref "U7") (pin "45") (pinfunction "(RXD1/INT2)PD2_45") (pintype "passive"))
    )
    (net (code "27") (name "/PD3") (class "Default")
      (node (ref "R53") (pin "2") (pinfunction "2_2") (pintype "passive"))
      (node (ref "U19") (pin "10") (pinfunction "Collector4_10") (pintype "passive"))
      (node (ref "U7") (pin "46") (pinfunction "(TXD1/INT3)PD3_46") (pintype "passive"))
    )
    (net (code "28") (name "/PD7") (class "Default")
      (node (ref "U14") (pin "6") (pinfunction "Cathode3_6") (pintype "passive"))
      (node (ref "U7") (pin "50") (pinfunction "(T0)PD7_50") (pintype "passive"))
    )
    (net (code "29") (name "/PE0_RX0") (class "Default")
      (node (ref "P11") (pin "3") (pinfunction "3_3") (pintype "passive"))
      (node (ref "U7") (pin "2") (pinfunction "(RXD0/PCIN8)PE0_2") (pintype "passive"))
    )
    (net (code "30") (name "/PE1_TX0") (class "Default")
      (node (ref "P11") (pin "2") (pinfunction "2_2") (pintype "passive"))
      (node (ref "U7") (pin "3") (pinfunction "(TXD0)PE1_3") (pintype "passive"))
    )
    (net (code "31") (name "/PE3") (class "Default")
      (node (ref "U5") (pin "3") (pinfunction "IN1_3") (pintype "passive"))
      (node (ref "U7") (pin "5") (pinfunction "(OC3A/AIN1)PE3_5") (pintype "passive"))
    )
    (net (code "32") (name "/PE4") (class "Default")
      (node (ref "R51") (pin "2") (pinfunction "2_2") (pintype "passive"))
      (node (ref "U19") (pin "12") (pinfunction "Collector3_12") (pintype "passive"))
      (node (ref "U7") (pin "6") (pinfunction "(OC3B/INT4)PE4_6") (pintype "passive"))
    )
    (net (code "33") (name "/PE5") (class "Default")
      (node (ref "R34") (pin "1") (pinfunction "1_1") (pintype "passive"))
      (node (ref "U16") (pin "4") (pinfunction "4_4") (pintype "passive"))
      (node (ref "U7") (pin "7") (pinfunction "(OC3C/INT5)PE5_7") (pintype "passive"))
    )
    (net (code "34") (name "/PF6") (class "Default")
      (node (ref "R35") (pin "2") (pinfunction "2_2") (pintype "passive"))
      (node (ref "U6") (pin "8") (pinfunction "OE_8") (pintype "passive"))
      (node (ref "U7") (pin "91") (pinfunction "(ADC6/TDO)PF6_91") (pintype "passive"))
    )
    (net (code "35") (name "/PG5") (class "Default")
      (node (ref "U5") (pin "2") (pinfunction "IN2_2") (pintype "passive"))
      (node (ref "U7") (pin "1") (pinfunction "(OC0B)PG5_1") (pintype "passive"))
    )
    (net (code "36") (name "/PH0_RXD2") (class "Default")
      (node (ref "U6") (pin "13") (pinfunction "B1_13") (pintype "passive"))
      (node (ref "U7") (pin "12") (pinfunction "PH0(RXD2)_12") (pintype "passive"))
    )
    (net (code "37") (name "/PH1_TXD2") (class "Default")
      (node (ref "U6") (pin "12") (pinfunction "B2_12") (pintype "passive"))
      (node (ref "U7") (pin "13") (pinfunction "PH1(TXD2)_13") (pintype "passive"))
    )
    (net (code "38") (name "/PH5") (class "Default")
      (node (ref "U2") (pin "3") (pinfunction "IN1_3") (pintype "passive"))
      (node (ref "U7") (pin "17") (pinfunction "PH5(OC4C)_17") (pintype "passive"))
    )
    (net (code "39") (name "/PH6") (class "Default")
      (node (ref "U14") (pin "8") (pinfunction "Cathode4_8") (pintype "passive"))
      (node (ref "U7") (pin "18") (pinfunction "PH6(OC2B)_18") (pintype "passive"))
    )
    (net (code "40") (name "/PJ0_RX3") (class "Default")
      (node (ref "P6") (pin "2") (pinfunction "2_2") (pintype "passive"))
      (node (ref "U7") (pin "63") (pinfunction "PJ0(RXD3/PCINT9)_63") (pintype "passive"))
    )
    (net (code "41") (name "/PJ1_TX3") (class "Default")
      (node (ref "P6") (pin "1") (pinfunction "1_1") (pintype "passive"))
      (node (ref "U7") (pin "64") (pinfunction "PJ1(TXD3/PCINT10)_64") (pintype "passive"))
    )
    (net (code "42") (name "/PK1") (class "Default")
      (node (ref "R37") (pin "1") (pinfunction "1_1") (pintype "passive"))
      (node (ref "U17") (pin "4") (pinfunction "4_4") (pintype "passive"))
      (node (ref "U7") (pin "88") (pinfunction "PK1(ADC9/PCINT17)_88") (pintype "passive"))
    )
    (net (code "43") (name "/PK3") (class "Default")
      (node (ref "U6") (pin "10") (pinfunction "B4_10") (pintype "passive"))
      (node (ref "U7") (pin "86") (pinfunction "PK3(ADC11/PCINT19)_86") (pintype "passive"))
    )
    (net (code "44") (name "/RESET") (class "Default")
      (node (ref "C4") (pin "1") (pinfunction "1_1") (pintype "passive"))
      (node (ref "P10") (pin "5") (pinfunction "5_5") (pintype "passive"))
      (node (ref "R9") (pin "1") (pinfunction "1_1") (pintype "passive"))
      (node (ref "U7") (pin "30") (pinfunction "~{RESET}_30") (pintype "passive"))
    )
    (net (code "45") (name "/霍尔") (class "Default")
      (node (ref "C41") (pin "1") (pinfunction "1_1") (pintype "passive"))
      (node (ref "P5") (pin "2") (pinfunction "OUT_2") (pintype "passive"))
      (node (ref "R42") (pin "2") (pinfunction "2_2") (pintype "passive"))
      (node (ref "U14") (pin "2") (pinfunction "Cathode1_2") (pintype "passive"))
    )
    (net (code "46") (name "AGND") (class "Default")
      (node (ref "C24") (pin "1") (pinfunction "1_1") (pintype "passive"))
      (node (ref "C25") (pin "2") (pinfunction "2_2") (pintype "passive"))
      (node (ref "C26") (pin "1") (pinfunction "1_1") (pintype "passive"))
      (node (ref "C27") (pin "1") (pinfunction "1_1") (pintype "passive"))
      (node (ref "C29") (pin "2") (pinfunction "2_2") (pintype "passive"))
      (node (ref "C41") (pin "2") (pinfunction "2_2") (pintype "passive"))
      (node (ref "L6") (pin "2") (pinfunction "2_2") (pintype "passive"))
      (node (ref "LS1") (pin "2") (pinfunction "B_2") (pintype "passive"))
      (node (ref "P5") (pin "1") (pinfunction "GND_1") (pintype "passive"))
      (node (ref "R22") (pin "1") (pinfunction "1_1") (pintype "passive"))
      (node (ref "R23") (pin "2") (pinfunction "2_2") (pintype "passive"))
      (node (ref "U12") (pin "1") (pinfunction "GND_1") (pintype "passive"))
      (node (ref "U12") (pin "10") (pinfunction "GND_10") (pintype "passive"))
      (node (ref "U12") (pin "11") (pinfunction "GND_11") (pintype "passive"))
      (node (ref "U12") (pin "20") (pinfunction "GND_20") (pintype "passive"))
      (node (ref "U13") (pin "1") (pinfunction "GND_1") (pintype "passive"))
      (node (ref "U16") (pin "3") (pinfunction "3_3") (pintype "passive"))
      (node (ref "U17") (pin "3") (pinfunction "3_3") (pintype "passive"))
      (node (ref "U6") (pin "7") (pinfunction "GND_7") (pintype "passive"))
    )
    (net (code "47") (name "GND") (class "Default")
      (node (ref "C13") (pin "2") (pinfunction "2_2") (pintype "passive"))
      (node (ref "C14") (pin "2") (pinfunction "2_2") (pintype "passive"))
      (node (ref "C15") (pin "2") (pinfunction "2_2") (pintype "passive"))
      (node (ref "C16") (pin "2") (pinfunction "2_2") (pintype "passive"))
      (node (ref "C18") (pin "2") (pinfunction "2_2") (pintype "passive"))
      (node (ref "C2") (pin "2") (pinfunction "2_2") (pintype "passive"))
      (node (ref "C20") (pin "1") (pinfunction "1_1") (pintype "passive"))
      (node (ref "C21") (pin "1") (pinfunction "1_1") (pintype "passive"))
      (node (ref "C22") (pin "2") (pinfunction "2_2") (pintype "passive"))
      (node (ref "C23") (pin "2") (pinfunction "2_2") (pintype "passive"))
      (node (ref "C28") (pin "2") (pinfunction "2_2") (pintype "passive"))
      (node (ref "C3") (pin "2") (pinfunction "2_2") (pintype "passive"))
      (node (ref "C30") (pin "1") (pinfunction "1_1") (pintype "passive"))
      (node (ref "C31") (pin "2") (pinfunction "2_2") (pintype "passive"))
      (node (ref "C32") (pin "2") (pinfunction "2_2") (pintype "passive"))
      (node (ref "C33") (pin "1") (pinfunction "1_1") (pintype "passive"))
      (node (ref "C34") (pin "1") (pinfunction "1_1") (pintype "passive"))
      (node (ref "C40") (pin "2") (pinfunction "2_2") (pintype "passive"))
      (node (ref "C5") (pin "2") (pinfunction "2_2") (pintype "passive"))
      (node (ref "C7") (pin "2") (pinfunction "2_2") (pintype "passive"))
      (node (ref "D4") (pin "1") (pinfunction "A_1") (pintype "passive"))
      (node (ref "L5") (pin "1") (pinfunction "1_1") (pintype "passive"))
      (node (ref "L6") (pin "1") (pinfunction "1_1") (pintype "passive"))
      (node (ref "P1") (pin "5") (pinfunction "GND_5") (pintype "passive"))
      (node (ref "P12") (pin "2") (pinfunction "2_2") (pintype "passive"))
      (node (ref "P13") (pin "5") (pinfunction "GND_5") (pintype "passive"))
      (node (ref "P17") (pin "3") (pinfunction "蓝_3") (pintype "passive"))
      (node (ref "P2") (pin "2") (pinfunction "2_2") (pintype "passive"))
      (node (ref "P3") (pin "2") (pinfunction "GND_2") (pintype "passive"))
      (node (ref "P4") (pin "3") (pinfunction "蓝_3") (pintype "passive"))
      (node (ref "P7") (pin "5") (pinfunction "GND_5") (pintype "passive"))
      (node (ref "R11") (pin "1") (pinfunction "1_1") (pintype "passive"))
      (node (ref "R13") (pin "1") (pinfunction "1_1") (pintype "passive"))
      (node (ref "R16") (pin "2") (pinfunction "2_2") (pintype "passive"))
      (node (ref "R19") (pin "1") (pinfunction "1_1") (pintype "passive"))
      (node (ref "R20") (pin "1") (pinfunction "1_1") (pintype "passive"))
      (node (ref "R21") (pin "1") (pinfunction "1_1") (pintype "passive"))
      (node (ref "R24") (pin "1") (pinfunction "1_1") (pintype "passive"))
      (node (ref "R26") (pin "1") (pinfunction "1_1") (pintype "passive"))
      (node (ref "R3") (pin "1") (pinfunction "1_1") (pintype "passive"))
      (node (ref "R4") (pin "1") (pinfunction "1_1") (pintype "passive"))
      (node (ref "U1") (pin "1") (pinfunction "GND_1") (pintype "passive"))
      (node (ref "U10") (pin "7") (pinfunction "GND_7") (pintype "passive"))
      (node (ref "U11") (pin "1") (pinfunction "GND_1") (pintype "passive"))
      (node (ref "U14") (pin "11") (pinfunction "Emitter3_11") (pintype "passive"))
      (node (ref "U14") (pin "13") (pinfunction "Emitter2_13") (pintype "passive"))
      (node (ref "U14") (pin "9") (pinfunction "Emitter4_9") (pintype "passive"))
      (node (ref "U2") (pin "1") (pinfunction "GND_1") (pintype "passive"))
      (node (ref "U5") (pin "1") (pinfunction "GND_1") (pintype "passive"))
      (node (ref "U8") (pin "1") (pinfunction "GND_1") (pintype "passive"))
      (node (ref "U9") (pin "2") (pinfunction "GND_2") (pintype "passive"))
    )
    (net (code "48") (name "GND2") (class "Default")
      (node (ref "C11") (pin "2") (pinfunction "2_2") (pintype "passive"))
      (node (ref "C35") (pin "1") (pinfunction "1_1") (pintype "passive"))
      (node (ref "C36") (pin "2") (pinfunction "2_2") (pintype "passive"))
      (node (ref "C37") (pin "1") (pinfunction "1_1") (pintype "passive"))
      (node (ref "C38") (pin "2") (pinfunction "2_2") (pintype "passive"))
      (node (ref "C39") (pin "1") (pinfunction "1_1") (pintype "passive"))
      (node (ref "C4") (pin "2") (pinfunction "2_2") (pintype "passive"))
      (node (ref "C42") (pin "2") (pinfunction "2_2") (pintype "passive"))
      (node (ref "C45") (pin "1") (pinfunction "1_1") (pintype "passive"))
      (node (ref "C6") (pin "2") (pinfunction "2_2") (pintype "passive"))
      (node (ref "C8") (pin "2") (pinfunction "2_2") (pintype "passive"))
      (node (ref "C9") (pin "2") (pinfunction "2_2") (pintype "passive"))
      (node (ref "D1") (pin "1") (pinfunction "A_1") (pintype "passive"))
      (node (ref "D5") (pin "2") (pinfunction "K_2") (pintype "passive"))
      (node (ref "L5") (pin "2") (pinfunction "2_2") (pintype "passive"))
      (node (ref "P10") (pin "6") (pinfunction "6_6") (pintype "passive"))
      (node (ref "P11") (pin "4") (pinfunction "4_4") (pintype "passive"))
      (node (ref "P6") (pin "3") (pinfunction "3_3") (pintype "passive"))
      (node (ref "R35") (pin "1") (pinfunction "1_1") (pintype "passive"))
      (node (ref "U14") (pin "15") (pinfunction "Emitter1_15") (pintype "passive"))
      (node (ref "U15") (pin "2") (pinfunction "GND_2") (pintype "passive"))
      (node (ref "U19") (pin "11") (pinfunction "Emitter3_11") (pintype "passive"))
      (node (ref "U19") (pin "13") (pinfunction "Emitter2_13") (pintype "passive"))
      (node (ref "U19") (pin "15") (pinfunction "Emitter1_15") (pintype "passive"))
      (node (ref "U19") (pin "9") (pinfunction "Emitter4_9") (pintype "passive"))
      (node (ref "U7") (pin "11") (pinfunction "GND_11") (pintype "passive"))
      (node (ref "U7") (pin "32") (pinfunction "GND_32") (pintype "passive"))
      (node (ref "U7") (pin "62") (pinfunction "GND_62") (pintype "passive"))
      (node (ref "U7") (pin "81") (pinfunction "GND_81") (pintype "passive"))
      (node (ref "U7") (pin "99") (pinfunction "AGND_99") (pintype "passive"))
    )
    (net (code "49") (name "Net-(C19-Pad2)") (class "Default")
      (node (ref "C19") (pin "2") (pinfunction "2_2") (pintype "passive"))
      (node (ref "R20") (pin "2") (pinfunction "2_2") (pintype "passive"))
    )
    (net (code "50") (name "Net-(D2-A)") (class "Default")
      (node (ref "D2") (pin "1") (pinfunction "A_1") (pintype "passive"))
      (node (ref "R8") (pin "1") (pinfunction "1_1") (pintype "passive"))
    )
    (net (code "51") (name "Net-(D3-A)") (class "Default")
      (node (ref "D3") (pin "1") (pinfunction "A_1") (pintype "passive"))
      (node (ref "L1") (pin "2") (pinfunction "2_2") (pintype "passive"))
      (node (ref "U9") (pin "1") (pinfunction "SW_1") (pintype "passive"))
    )
    (net (code "52") (name "Net-(D4-K)") (class "Default")
      (node (ref "C17") (pin "2") (pinfunction "2_2") (pintype "passive"))
      (node (ref "D4") (pin "3") (pinfunction "K_3") (pintype "passive"))
      (node (ref "L2") (pin "1") (pinfunction "1_1") (pintype "passive"))
      (node (ref "U10") (pin "8") (pinfunction "PH_8") (pintype "passive"))
    )
    (net (code "53") (name "Net-(D6-K)") (class "Default")
      (node (ref "D6") (pin "2") (pinfunction "K_2") (pintype "passive"))
      (node (ref "R23") (pin "1") (pinfunction "1_1") (pintype "passive"))
    )
    (net (code "54") (name "Net-(F1-Pad1)") (class "Default")
      (node (ref "F1") (pin "1") (pinfunction "1_1") (pintype "passive"))
      (node (ref "P12") (pin "1") (pinfunction "1_1") (pintype "passive"))
    )
    (net (code "55") (name "Net-(LS1-A)") (class "Default")
      (node (ref "LS1") (pin "1") (pinfunction "A_1") (pintype "passive"))
      (node (ref "Q1") (pin "3") (pinfunction "C_3") (pintype "passive"))
    )
    (net (code "56") (name "Net-(P1-M+)") (class "Default")
      (node (ref "P1") (pin "6") (pinfunction "M+_6") (pintype "passive"))
      (node (ref "U1") (pin "8") (pinfunction "OUT2_8") (pintype "passive"))
    )
    (net (code "57") (name "Net-(P1-M-)") (class "Default")
      (node (ref "P1") (pin "1") (pinfunction "M-_1") (pintype "passive"))
      (node (ref "U1") (pin "6") (pinfunction "OUT1_6") (pintype "passive"))
    )
    (net (code "58") (name "Net-(P3-M+)") (class "Default")
      (node (ref "P3") (pin "6") (pinfunction "M+_6") (pintype "passive"))
      (node (ref "U2") (pin "8") (pinfunction "OUT2_8") (pintype "passive"))
    )
    (net (code "59") (name "Net-(P3-M-)") (class "Default")
      (node (ref "P3") (pin "1") (pinfunction "M-_1") (pintype "passive"))
      (node (ref "U2") (pin "6") (pinfunction "OUT1_6") (pintype "passive"))
    )
    (net (code "60") (name "Net-(P4-黑)") (class "Default")
      (node (ref "P4") (pin "2") (pinfunction "黑_2") (pintype "passive"))
      (node (ref "R36") (pin "2") (pinfunction "2_2") (pintype "passive"))
      (node (ref "U17") (pin "2") (pinfunction "2_2") (pintype "passive"))
    )
    (net (code "61") (name "Net-(P7-M+)") (class "Default")
      (node (ref "P7") (pin "6") (pinfunction "M+_6") (pintype "passive"))
      (node (ref "U5") (pin "8") (pinfunction "OUT2_8") (pintype "passive"))
    )
    (net (code "62") (name "Net-(P7-M-)") (class "Default")
      (node (ref "P7") (pin "1") (pinfunction "M-_1") (pintype "passive"))
      (node (ref "U5") (pin "6") (pinfunction "OUT1_6") (pintype "passive"))
    )
    (net (code "63") (name "Net-(P13-M+)") (class "Default")
      (node (ref "P13") (pin "1") (pinfunction "M+_1") (pintype "passive"))
      (node (ref "U11") (pin "4") (pinfunction "OUT_4") (pintype "passive"))
      (node (ref "U11") (pin "8") (pinfunction "OUT_8") (pintype "passive"))
    )
    (net (code "64") (name "Net-(P13-M-)") (class "Default")
      (node (ref "P13") (pin "6") (pinfunction "M-_6") (pintype "passive"))
      (node (ref "U8") (pin "4") (pinfunction "OUT_4") (pintype "passive"))
      (node (ref "U8") (pin "8") (pinfunction "OUT_8") (pintype "passive"))
    )
    (net (code "65") (name "Net-(P17-黑)") (class "Default")
      (node (ref "P17") (pin "2") (pinfunction "黑_2") (pintype "passive"))
      (node (ref "R33") (pin "2") (pinfunction "2_2") (pintype "passive"))
      (node (ref "U16") (pin "2") (pinfunction "2_2") (pintype "passive"))
    )
    (net (code "66") (name "Net-(Q1-B)") (class "Default")
      (node (ref "Q1") (pin "1") (pinfunction "B_1") (pintype "passive"))
      (node (ref "R12") (pin "1") (pinfunction "1_1") (pintype "passive"))
    )
    (net (code "67") (name "Net-(R1-Pad2)") (class "Default")
      (node (ref "R1") (pin "2") (pinfunction "2_2") (pintype "passive"))
      (node (ref "U17") (pin "1") (pinfunction "1_1") (pintype "passive"))
    )
    (net (code "68") (name "Net-(R32-Pad2)") (class "Default")
      (node (ref "R32") (pin "2") (pinfunction "2_2") (pintype "passive"))
      (node (ref "U16") (pin "1") (pinfunction "1_1") (pintype "passive"))
    )
    (net (code "69") (name "Net-(U1-ISEN)") (class "Default")
      (node (ref "R3") (pin "2") (pinfunction "2_2") (pintype "passive"))
      (node (ref "U1") (pin "7") (pinfunction "ISEN_7") (pintype "passive"))
    )
    (net (code "70") (name "Net-(U1-nFAULT)") (class "Default")
      (node (ref "R27") (pin "2") (pinfunction "2_2") (pintype "passive"))
      (node (ref "U1") (pin "4") (pinfunction "nFAULT_4") (pintype "passive"))
    )
    (net (code "71") (name "Net-(U2-ISEN)") (class "Default")
      (node (ref "R4") (pin "2") (pinfunction "2_2") (pintype "passive"))
      (node (ref "U2") (pin "7") (pinfunction "ISEN_7") (pintype "passive"))
    )
    (net (code "72") (name "Net-(U2-nFAULT)") (class "Default")
      (node (ref "R25") (pin "2") (pinfunction "2_2") (pintype "passive"))
      (node (ref "U2") (pin "4") (pinfunction "nFAULT_4") (pintype "passive"))
    )
    (net (code "73") (name "Net-(U5-ISEN)") (class "Default")
      (node (ref "R11") (pin "2") (pinfunction "2_2") (pintype "passive"))
      (node (ref "U5") (pin "7") (pinfunction "ISEN_7") (pintype "passive"))
    )
    (net (code "74") (name "Net-(U5-nFAULT)") (class "Default")
      (node (ref "R28") (pin "2") (pinfunction "2_2") (pintype "passive"))
      (node (ref "U5") (pin "4") (pinfunction "nFAULT_4") (pintype "passive"))
    )
    (net (code "75") (name "Net-(U7-AREF)") (class "Default")
      (node (ref "C9") (pin "1") (pinfunction "1_1") (pintype "passive"))
      (node (ref "U7") (pin "98") (pinfunction "AREF_98") (pintype "passive"))
    )
    (net (code "76") (name "Net-(U7-XTAL1)") (class "Default")
      (node (ref "C8") (pin "1") (pinfunction "1_1") (pintype "passive"))
      (node (ref "R45") (pin "2") (pinfunction "2_2") (pintype "passive"))
      (node (ref "U7") (pin "34") (pinfunction "XTAL1_34") (pintype "passive"))
      (node (ref "Y1") (pin "2") (pinfunction "OSC2_2") (pintype "passive"))
    )
    (net (code "77") (name "Net-(U7-XTAL2)") (class "Default")
      (node (ref "C6") (pin "1") (pinfunction "1_1") (pintype "passive"))
      (node (ref "R45") (pin "1") (pinfunction "1_1") (pintype "passive"))
      (node (ref "U7") (pin "33") (pinfunction "XTAL2_33") (pintype "passive"))
      (node (ref "Y1") (pin "1") (pinfunction "OSC1_1") (pintype "passive"))
    )
    (net (code "78") (name "Net-(U8-IN)") (class "Default")
      (node (ref "R30") (pin "2") (pinfunction "2_2") (pintype "passive"))
      (node (ref "U8") (pin "2") (pinfunction "IN_2") (pintype "passive"))
    )
    (net (code "79") (name "Net-(U8-INH)") (class "Default")
      (node (ref "R31") (pin "2") (pinfunction "2_2") (pintype "passive"))
      (node (ref "U8") (pin "3") (pinfunction "INH_3") (pintype "passive"))
    )
    (net (code "80") (name "Net-(U8-IS)") (class "Default")
      (node (ref "R26") (pin "2") (pinfunction "2_2") (pintype "passive"))
      (node (ref "U8") (pin "6") (pinfunction "IS_6") (pintype "passive"))
    )
    (net (code "81") (name "Net-(U8-SR)") (class "Default")
      (node (ref "R24") (pin "2") (pinfunction "2_2") (pintype "passive"))
      (node (ref "U8") (pin "5") (pinfunction "SR_5") (pintype "passive"))
    )
    (net (code "82") (name "Net-(U9-FB)") (class "Default")
      (node (ref "R15") (pin "2") (pinfunction "2_2") (pintype "passive"))
      (node (ref "R16") (pin "1") (pinfunction "1_1") (pintype "passive"))
      (node (ref "U9") (pin "3") (pinfunction "FB_3") (pintype "passive"))
    )
    (net (code "83") (name "Net-(U10-BOOT)") (class "Default")
      (node (ref "C17") (pin "1") (pinfunction "1_1") (pintype "passive"))
      (node (ref "U10") (pin "1") (pinfunction "BOOT_1") (pintype "passive"))
    )
    (net (code "84") (name "Net-(U10-COMP)") (class "Default")
      (node (ref "C19") (pin "1") (pinfunction "1_1") (pintype "passive"))
      (node (ref "C22") (pin "1") (pinfunction "1_1") (pintype "passive"))
      (node (ref "U10") (pin "6") (pinfunction "COMP_6") (pintype "passive"))
    )
    (net (code "85") (name "Net-(U10-EN)") (class "Default")
      (node (ref "R56") (pin "1") (pinfunction "1_1") (pintype "passive"))
      (node (ref "U10") (pin "3") (pinfunction "EN_3") (pintype "passive"))
    )
    (net (code "86") (name "Net-(U10-SS)") (class "Default")
      (node (ref "C23") (pin "1") (pinfunction "1_1") (pintype "passive"))
      (node (ref "U10") (pin "4") (pinfunction "SS_4") (pintype "passive"))
    )
    (net (code "87") (name "Net-(U10-VSENSE)") (class "Default")
      (node (ref "R17") (pin "1") (pinfunction "1_1") (pintype "passive"))
      (node (ref "R19") (pin "2") (pinfunction "2_2") (pintype "passive"))
      (node (ref "U10") (pin "5") (pinfunction "VSENSE_5") (pintype "passive"))
    )
    (net (code "88") (name "Net-(U11-IN)") (class "Default")
      (node (ref "R14") (pin "1") (pinfunction "1_1") (pintype "passive"))
      (node (ref "U11") (pin "2") (pinfunction "IN_2") (pintype "passive"))
    )
    (net (code "89") (name "Net-(U11-INH)") (class "Default")
      (node (ref "R29") (pin "1") (pinfunction "1_1") (pintype "passive"))
      (node (ref "U11") (pin "3") (pinfunction "INH_3") (pintype "passive"))
    )
    (net (code "90") (name "Net-(U11-IS)") (class "Default")
      (node (ref "R21") (pin "2") (pinfunction "2_2") (pintype "passive"))
      (node (ref "U11") (pin "6") (pinfunction "IS_6") (pintype "passive"))
    )
    (net (code "91") (name "Net-(U11-SR)") (class "Default")
      (node (ref "R13") (pin "2") (pinfunction "2_2") (pintype "passive"))
      (node (ref "U11") (pin "5") (pinfunction "SR_5") (pintype "passive"))
    )
    (net (code "92") (name "Net-(U12-M0)") (class "Default")
      (node (ref "U12") (pin "3") (pinfunction "M0_3") (pintype "passive"))
      (node (ref "U6") (pin "5") (pinfunction "A4_5") (pintype "passive"))
    )
    (net (code "93") (name "Net-(U12-M1)") (class "Default")
      (node (ref "U12") (pin "4") (pinfunction "M1_4") (pintype "passive"))
      (node (ref "U6") (pin "4") (pinfunction "A3_4") (pintype "passive"))
    )
    (net (code "94") (name "Net-(U12-RXD)") (class "Default")
      (node (ref "U12") (pin "6") (pinfunction "RXD_6") (pintype "passive"))
      (node (ref "U6") (pin "3") (pinfunction "A2_3") (pintype "passive"))
    )
    (net (code "95") (name "Net-(U12-TXD)") (class "Default")
      (node (ref "U12") (pin "7") (pinfunction "TXD_7") (pintype "passive"))
      (node (ref "U6") (pin "2") (pinfunction "A1_2") (pintype "passive"))
    )
    (net (code "96") (name "Net-(U14-Anode1)") (class "Default")
      (node (ref "R40") (pin "1") (pinfunction "1_1") (pintype "passive"))
      (node (ref "U14") (pin "1") (pinfunction "Anode1_1") (pintype "passive"))
    )
    (net (code "97") (name "Net-(U14-Anode2)") (class "Default")
      (node (ref "R41") (pin "1") (pinfunction "1_1") (pintype "passive"))
      (node (ref "U14") (pin "3") (pinfunction "Anode2_3") (pintype "passive"))
    )
    (net (code "98") (name "Net-(U14-Anode3)") (class "Default")
      (node (ref "R44") (pin "1") (pinfunction "1_1") (pintype "passive"))
      (node (ref "U14") (pin "5") (pinfunction "Anode3_5") (pintype "passive"))
    )
    (net (code "99") (name "Net-(U14-Anode4)") (class "Default")
      (node (ref "R54") (pin "1") (pinfunction "1_1") (pintype "passive"))
      (node (ref "U14") (pin "7") (pinfunction "Anode4_7") (pintype "passive"))
    )
    (net (code "100") (name "Net-(U15-Vin)") (class "Default")
      (node (ref "C36") (pin "1") (pinfunction "1_1") (pintype "passive"))
      (node (ref "C37") (pin "2") (pinfunction "2_2") (pintype "passive"))
      (node (ref "L4") (pin "2") (pinfunction "2_2") (pintype "passive"))
      (node (ref "U15") (pin "1") (pinfunction "Vin_1") (pintype "passive"))
    )
    (net (code "101") (name "Net-(U19-Anode1)") (class "Default")
      (node (ref "R46") (pin "1") (pinfunction "1_1") (pintype "passive"))
      (node (ref "U19") (pin "1") (pinfunction "Anode1_1") (pintype "passive"))
    )
    (net (code "102") (name "Net-(U19-Anode2)") (class "Default")
      (node (ref "R47") (pin "1") (pinfunction "1_1") (pintype "passive"))
      (node (ref "U19") (pin "3") (pinfunction "Anode2_3") (pintype "passive"))
    )
    (net (code "103") (name "Net-(U19-Anode3)") (class "Default")
      (node (ref "R48") (pin "1") (pinfunction "1_1") (pintype "passive"))
      (node (ref "U19") (pin "5") (pinfunction "Anode3_5") (pintype "passive"))
    )
    (net (code "104") (name "Net-(U19-Anode4)") (class "Default")
      (node (ref "R52") (pin "1") (pinfunction "1_1") (pintype "passive"))
      (node (ref "U19") (pin "7") (pinfunction "Anode4_7") (pintype "passive"))
    )
    (net (code "105") (name "VCC") (class "Default")
      (node (ref "C14") (pin "1") (pinfunction "1_1") (pintype "passive"))
      (node (ref "C18") (pin "1") (pinfunction "1_1") (pintype "passive"))
      (node (ref "C2") (pin "1") (pinfunction "1_1") (pintype "passive"))
      (node (ref "C3") (pin "1") (pinfunction "1_1") (pintype "passive"))
      (node (ref "C30") (pin "2") (pinfunction "2_2") (pintype "passive"))
      (node (ref "C31") (pin "1") (pinfunction "1_1") (pintype "passive"))
      (node (ref "C32") (pin "1") (pinfunction "1_1") (pintype "passive"))
      (node (ref "C33") (pin "2") (pinfunction "2_2") (pintype "passive"))
      (node (ref "C5") (pin "1") (pinfunction "1_1") (pintype "passive"))
      (node (ref "C7") (pin "1") (pinfunction "1_1") (pintype "passive"))
      (node (ref "F1") (pin "2") (pinfunction "2_2") (pintype "passive"))
      (node (ref "L1") (pin "1") (pinfunction "1_1") (pintype "passive"))
      (node (ref "L4") (pin "1") (pinfunction "1_1") (pintype "passive"))
      (node (ref "P17") (pin "1") (pinfunction "棕_1") (pintype "passive"))
      (node (ref "P4") (pin "1") (pinfunction "棕_1") (pintype "passive"))
      (node (ref "R1") (pin "1") (pinfunction "1_1") (pintype "passive"))
      (node (ref "R18") (pin "2") (pinfunction "2_2") (pintype "passive"))
      (node (ref "R32") (pin "1") (pinfunction "1_1") (pintype "passive"))
      (node (ref "R33") (pin "1") (pinfunction "1_1") (pintype "passive"))
      (node (ref "R36") (pin "1") (pinfunction "1_1") (pintype "passive"))
      (node (ref "R56") (pin "2") (pinfunction "2_2") (pintype "passive"))
      (node (ref "U1") (pin "5") (pinfunction "VM_5") (pintype "passive"))
      (node (ref "U10") (pin "2") (pinfunction "VIN_2") (pintype "passive"))
      (node (ref "U11") (pin "7") (pinfunction "VS_7") (pintype "passive"))
      (node (ref "U2") (pin "5") (pinfunction "VM_5") (pintype "passive"))
      (node (ref "U5") (pin "5") (pinfunction "VM_5") (pintype "passive"))
      (node (ref "U8") (pin "7") (pinfunction "VS_7") (pintype "passive"))
      (node (ref "U9") (pin "4") (pinfunction "EN_4") (pintype "passive"))
      (node (ref "U9") (pin "5") (pinfunction "VIN_5") (pintype "passive"))
    )
    (net (code "106") (name "unconnected-(P1-B-Pad4)") (class "Default")
      (node (ref "P1") (pin "4") (pinfunction "B_4") (pintype "passive+no_connect"))
    )
    (net (code "107") (name "unconnected-(P3-B-Pad4)") (class "Default")
      (node (ref "P3") (pin "4") (pinfunction "B_4") (pintype "passive+no_connect"))
    )
    (net (code "108") (name "unconnected-(P7-B-Pad4)") (class "Default")
      (node (ref "P7") (pin "4") (pinfunction "B_4") (pintype "passive+no_connect"))
    )
    (net (code "109") (name "unconnected-(P13-B-Pad4)") (class "Default")
      (node (ref "P13") (pin "4") (pinfunction "B_4") (pintype "passive+no_connect"))
    )
    (net (code "110") (name "unconnected-(U6-NC-Pad6)") (class "Default")
      (node (ref "U6") (pin "6") (pinfunction "NC_6") (pintype "passive+no_connect"))
    )
    (net (code "111") (name "unconnected-(U6-NC-Pad9)") (class "Default")
      (node (ref "U6") (pin "9") (pinfunction "NC_9") (pintype "passive+no_connect"))
    )
    (net (code "112") (name "unconnected-(U7-(A9)PC1-Pad54)") (class "Default")
      (node (ref "U7") (pin "54") (pinfunction "(A9)PC1_54") (pintype "passive"))
    )
    (net (code "113") (name "unconnected-(U7-(A10)PC2-Pad55)") (class "Default")
      (node (ref "U7") (pin "55") (pinfunction "(A10)PC2_55") (pintype "passive"))
    )
    (net (code "114") (name "unconnected-(U7-(A11)PC3-Pad56)") (class "Default")
      (node (ref "U7") (pin "56") (pinfunction "(A11)PC3_56") (pintype "passive"))
    )
    (net (code "115") (name "unconnected-(U7-(A12)PC4-Pad57)") (class "Default")
      (node (ref "U7") (pin "57") (pinfunction "(A12)PC4_57") (pintype "passive"))
    )
    (net (code "116") (name "unconnected-(U7-(A13)PC5-Pad58)") (class "Default")
      (node (ref "U7") (pin "58") (pinfunction "(A13)PC5_58") (pintype "passive"))
    )
    (net (code "117") (name "unconnected-(U7-(A14)PC6-Pad59)") (class "Default")
      (node (ref "U7") (pin "59") (pinfunction "(A14)PC6_59") (pintype "passive"))
    )
    (net (code "118") (name "unconnected-(U7-(A15)PC7-Pad60)") (class "Default")
      (node (ref "U7") (pin "60") (pinfunction "(A15)PC7_60") (pintype "passive"))
    )
    (net (code "119") (name "unconnected-(U7-(AD0)PA0-Pad78)") (class "Default")
      (node (ref "U7") (pin "78") (pinfunction "(AD0)PA0_78") (pintype "passive"))
    )
    (net (code "120") (name "unconnected-(U7-(AD1)PA1-Pad77)") (class "Default")
      (node (ref "U7") (pin "77") (pinfunction "(AD1)PA1_77") (pintype "passive"))
    )
    (net (code "121") (name "unconnected-(U7-(AD3)PA3-Pad75)") (class "Default")
      (node (ref "U7") (pin "75") (pinfunction "(AD3)PA3_75") (pintype "passive"))
    )
    (net (code "122") (name "unconnected-(U7-(AD4)PA4-Pad74)") (class "Default")
      (node (ref "U7") (pin "74") (pinfunction "(AD4)PA4_74") (pintype "passive"))
    )
    (net (code "123") (name "unconnected-(U7-(AD5)PA5-Pad73)") (class "Default")
      (node (ref "U7") (pin "73") (pinfunction "(AD5)PA5_73") (pintype "passive"))
    )
    (net (code "124") (name "unconnected-(U7-(AD7)PA7-Pad71)") (class "Default")
      (node (ref "U7") (pin "71") (pinfunction "(AD7)PA7_71") (pintype "passive"))
    )
    (net (code "125") (name "unconnected-(U7-(ADC0)PF0-Pad97)") (class "Default")
      (node (ref "U7") (pin "97") (pinfunction "(ADC0)PF0_97") (pintype "passive"))
    )
    (net (code "126") (name "unconnected-(U7-(ADC1)PF1-Pad96)") (class "Default")
      (node (ref "U7") (pin "96") (pinfunction "(ADC1)PF1_96") (pintype "passive"))
    )
    (net (code "127") (name "unconnected-(U7-(ADC2)PF2-Pad95)") (class "Default")
      (node (ref "U7") (pin "95") (pinfunction "(ADC2)PF2_95") (pintype "passive"))
    )
    (net (code "128") (name "unconnected-(U7-(ADC3)PF3-Pad94)") (class "Default")
      (node (ref "U7") (pin "94") (pinfunction "(ADC3)PF3_94") (pintype "passive"))
    )
    (net (code "129") (name "unconnected-(U7-(ADC4{slash}TCK)PF4-Pad93)") (class "Default")
      (node (ref "U7") (pin "93") (pinfunction "(ADC4/TCK)PF4_93") (pintype "passive"))
    )
    (net (code "130") (name "unconnected-(U7-(ADC5{slash}TMS)PF5-Pad92)") (class "Default")
      (node (ref "U7") (pin "92") (pinfunction "(ADC5/TMS)PF5_92") (pintype "passive"))
    )
    (net (code "131") (name "unconnected-(U7-(ADC7{slash}TDI)PF7-Pad90)") (class "Default")
      (node (ref "U7") (pin "90") (pinfunction "(ADC7/TDI)PF7_90") (pintype "passive"))
    )
    (net (code "132") (name "unconnected-(U7-(ALE)PG2-Pad70)") (class "Default")
      (node (ref "U7") (pin "70") (pinfunction "(ALE)PG2_70") (pintype "passive"))
    )
    (net (code "133") (name "unconnected-(U7-(CLKO{slash}ICP3{slash}INT7)PE7-Pad9)") (class "Default")
      (node (ref "U7") (pin "9") (pinfunction "(CLKO/ICP3/INT7)PE7_9") (pintype "passive"))
    )
    (net (code "134") (name "unconnected-(U7-(ICP1)PD4-Pad47)") (class "Default")
      (node (ref "U7") (pin "47") (pinfunction "(ICP1)PD4_47") (pintype "passive"))
    )
    (net (code "135") (name "unconnected-(U7-(RD)PG1-Pad52)") (class "Default")
      (node (ref "U7") (pin "52") (pinfunction "(RD)PG1_52") (pintype "passive"))
    )
    (net (code "136") (name "unconnected-(U7-(SS{slash}PCINT0)PB0-Pad19)") (class "Default")
      (node (ref "U7") (pin "19") (pinfunction "(SS/PCINT0)PB0_19") (pintype "passive"))
    )
    (net (code "137") (name "unconnected-(U7-(T1)PD6-Pad49)") (class "Default")
      (node (ref "U7") (pin "49") (pinfunction "(T1)PD6_49") (pintype "passive"))
    )
    (net (code "138") (name "unconnected-(U7-(T3{slash}INT6)PE6-Pad8)") (class "Default")
      (node (ref "U7") (pin "8") (pinfunction "(T3/INT6)PE6_8") (pintype "passive"))
    )
    (net (code "139") (name "unconnected-(U7-(TOSC1)PG4-Pad29)") (class "Default")
      (node (ref "U7") (pin "29") (pinfunction "(TOSC1)PG4_29") (pintype "passive"))
    )
    (net (code "140") (name "unconnected-(U7-(TOSC2)PG3-Pad28)") (class "Default")
      (node (ref "U7") (pin "28") (pinfunction "(TOSC2)PG3_28") (pintype "passive"))
    )
    (net (code "141") (name "unconnected-(U7-(WR)PG0-Pad51)") (class "Default")
      (node (ref "U7") (pin "51") (pinfunction "(WR)PG0_51") (pintype "passive"))
    )
    (net (code "142") (name "unconnected-(U7-(XCK0{slash}AIN0)PE2-Pad4)") (class "Default")
      (node (ref "U7") (pin "4") (pinfunction "(XCK0/AIN0)PE2_4") (pintype "passive"))
    )
    (net (code "143") (name "unconnected-(U7-(XCK1)PD5-Pad48)") (class "Default")
      (node (ref "U7") (pin "48") (pinfunction "(XCK1)PD5_48") (pintype "passive"))
    )
    (net (code "144") (name "unconnected-(U7-PH2(XCK2)-Pad14)") (class "Default")
      (node (ref "U7") (pin "14") (pinfunction "PH2(XCK2)_14") (pintype "passive"))
    )
    (net (code "145") (name "unconnected-(U7-PH3(OC4A)-Pad15)") (class "Default")
      (node (ref "U7") (pin "15") (pinfunction "PH3(OC4A)_15") (pintype "passive"))
    )
    (net (code "146") (name "unconnected-(U7-PH4(OC4B)-Pad16)") (class "Default")
      (node (ref "U7") (pin "16") (pinfunction "PH4(OC4B)_16") (pintype "passive"))
    )
    (net (code "147") (name "unconnected-(U7-PH7(T4)-Pad27)") (class "Default")
      (node (ref "U7") (pin "27") (pinfunction "PH7(T4)_27") (pintype "passive"))
    )
    (net (code "148") (name "unconnected-(U7-PJ2(XCK3{slash}PCINT11)-Pad65)") (class "Default")
      (node (ref "U7") (pin "65") (pinfunction "PJ2(XCK3/PCINT11)_65") (pintype "passive"))
    )
    (net (code "149") (name "unconnected-(U7-PJ3(PCINT12)-Pad66)") (class "Default")
      (node (ref "U7") (pin "66") (pinfunction "PJ3(PCINT12)_66") (pintype "passive"))
    )
    (net (code "150") (name "unconnected-(U7-PJ4(PCINT13)-Pad67)") (class "Default")
      (node (ref "U7") (pin "67") (pinfunction "PJ4(PCINT13)_67") (pintype "passive"))
    )
    (net (code "151") (name "unconnected-(U7-PJ5(PCINT14)-Pad68)") (class "Default")
      (node (ref "U7") (pin "68") (pinfunction "PJ5(PCINT14)_68") (pintype "passive"))
    )
    (net (code "152") (name "unconnected-(U7-PJ6(PCINT15)-Pad69)") (class "Default")
      (node (ref "U7") (pin "69") (pinfunction "PJ6(PCINT15)_69") (pintype "passive"))
    )
    (net (code "153") (name "unconnected-(U7-PJ7-Pad79)") (class "Default")
      (node (ref "U7") (pin "79") (pinfunction "PJ7_79") (pintype "passive"))
    )
    (net (code "154") (name "unconnected-(U7-PK2(ADC10{slash}PCINT18)-Pad87)") (class "Default")
      (node (ref "U7") (pin "87") (pinfunction "PK2(ADC10/PCINT18)_87") (pintype "passive"))
    )
    (net (code "155") (name "unconnected-(U7-PK5(ADC13{slash}PCINT21)-Pad84)") (class "Default")
      (node (ref "U7") (pin "84") (pinfunction "PK5(ADC13/PCINT21)_84") (pintype "passive"))
    )
    (net (code "156") (name "unconnected-(U7-PK6(ADC14{slash}PCINT22)-Pad83)") (class "Default")
      (node (ref "U7") (pin "83") (pinfunction "PK6(ADC14/PCINT22)_83") (pintype "passive"))
    )
    (net (code "157") (name "unconnected-(U7-PK7(ADC15{slash}PCINT23)-Pad82)") (class "Default")
      (node (ref "U7") (pin "82") (pinfunction "PK7(ADC15/PCINT23)_82") (pintype "passive"))
    )
    (net (code "158") (name "unconnected-(U7-PL0(ICP4)-Pad35)") (class "Default")
      (node (ref "U7") (pin "35") (pinfunction "PL0(ICP4)_35") (pintype "passive"))
    )
    (net (code "159") (name "unconnected-(U7-PL1(ICP5)-Pad36)") (class "Default")
      (node (ref "U7") (pin "36") (pinfunction "PL1(ICP5)_36") (pintype "passive"))
    )
    (net (code "160") (name "unconnected-(U7-PL2(T5)-Pad37)") (class "Default")
      (node (ref "U7") (pin "37") (pinfunction "PL2(T5)_37") (pintype "passive"))
    )
    (net (code "161") (name "unconnected-(U7-PL3(OC5A)-Pad38)") (class "Default")
      (node (ref "U7") (pin "38") (pinfunction "PL3(OC5A)_38") (pintype "passive"))
    )
    (net (code "162") (name "unconnected-(U7-PL4(OC5B)-Pad39)") (class "Default")
      (node (ref "U7") (pin "39") (pinfunction "PL4(OC5B)_39") (pintype "passive"))
    )
    (net (code "163") (name "unconnected-(U7-PL5(OC5C)-Pad40)") (class "Default")
      (node (ref "U7") (pin "40") (pinfunction "PL5(OC5C)_40") (pintype "passive"))
    )
    (net (code "164") (name "unconnected-(U7-PL6-Pad41)") (class "Default")
      (node (ref "U7") (pin "41") (pinfunction "PL6_41") (pintype "passive"))
    )
    (net (code "165") (name "unconnected-(U7-PL7-Pad42)") (class "Default")
      (node (ref "U7") (pin "42") (pinfunction "PL7_42") (pintype "passive"))
    )
    (net (code "166") (name "unconnected-(U9-NC-Pad6)") (class "Default")
      (node (ref "U9") (pin "6") (pinfunction "NC_6") (pintype "passive+no_connect"))
    )
    (net (code "167") (name "unconnected-(U12-AUX-Pad8)") (class "Default")
      (node (ref "U12") (pin "8") (pinfunction "AUX_8") (pintype "passive+no_connect"))
    )
    (net (code "168") (name "unconnected-(U12-NC-Pad2)") (class "Default")
      (node (ref "U12") (pin "2") (pinfunction "NC_2") (pintype "passive+no_connect"))
    )
    (net (code "169") (name "unconnected-(U12-NC-Pad12)") (class "Default")
      (node (ref "U12") (pin "12") (pinfunction "NC_12") (pintype "passive+no_connect"))
    )
    (net (code "170") (name "unconnected-(U12-NC-Pad13)") (class "Default")
      (node (ref "U12") (pin "13") (pinfunction "NC_13") (pintype "passive+no_connect"))
    )
    (net (code "171") (name "unconnected-(U12-NC-Pad14)") (class "Default")
      (node (ref "U12") (pin "14") (pinfunction "NC_14") (pintype "passive+no_connect"))
    )
    (net (code "172") (name "unconnected-(U12-NC-Pad15)") (class "Default")
      (node (ref "U12") (pin "15") (pinfunction "NC_15") (pintype "passive+no_connect"))
    )
    (net (code "173") (name "unconnected-(U12-NC-Pad16)") (class "Default")
      (node (ref "U12") (pin "16") (pinfunction "NC_16") (pintype "passive+no_connect"))
    )
    (net (code "174") (name "unconnected-(U12-NC-Pad17)") (class "Default")
      (node (ref "U12") (pin "17") (pinfunction "NC_17") (pintype "passive+no_connect"))
    )
    (net (code "175") (name "unconnected-(U12-NC-Pad18)") (class "Default")
      (node (ref "U12") (pin "18") (pinfunction "NC_18") (pintype "passive+no_connect"))
    )
    (net (code "176") (name "unconnected-(U12-NC-Pad19)") (class "Default")
      (node (ref "U12") (pin "19") (pinfunction "NC_19") (pintype "passive+no_connect"))
    )
  )
)
